# MOSFET_Board.net
KiCad netlist of a schematic drawn in EAGLE
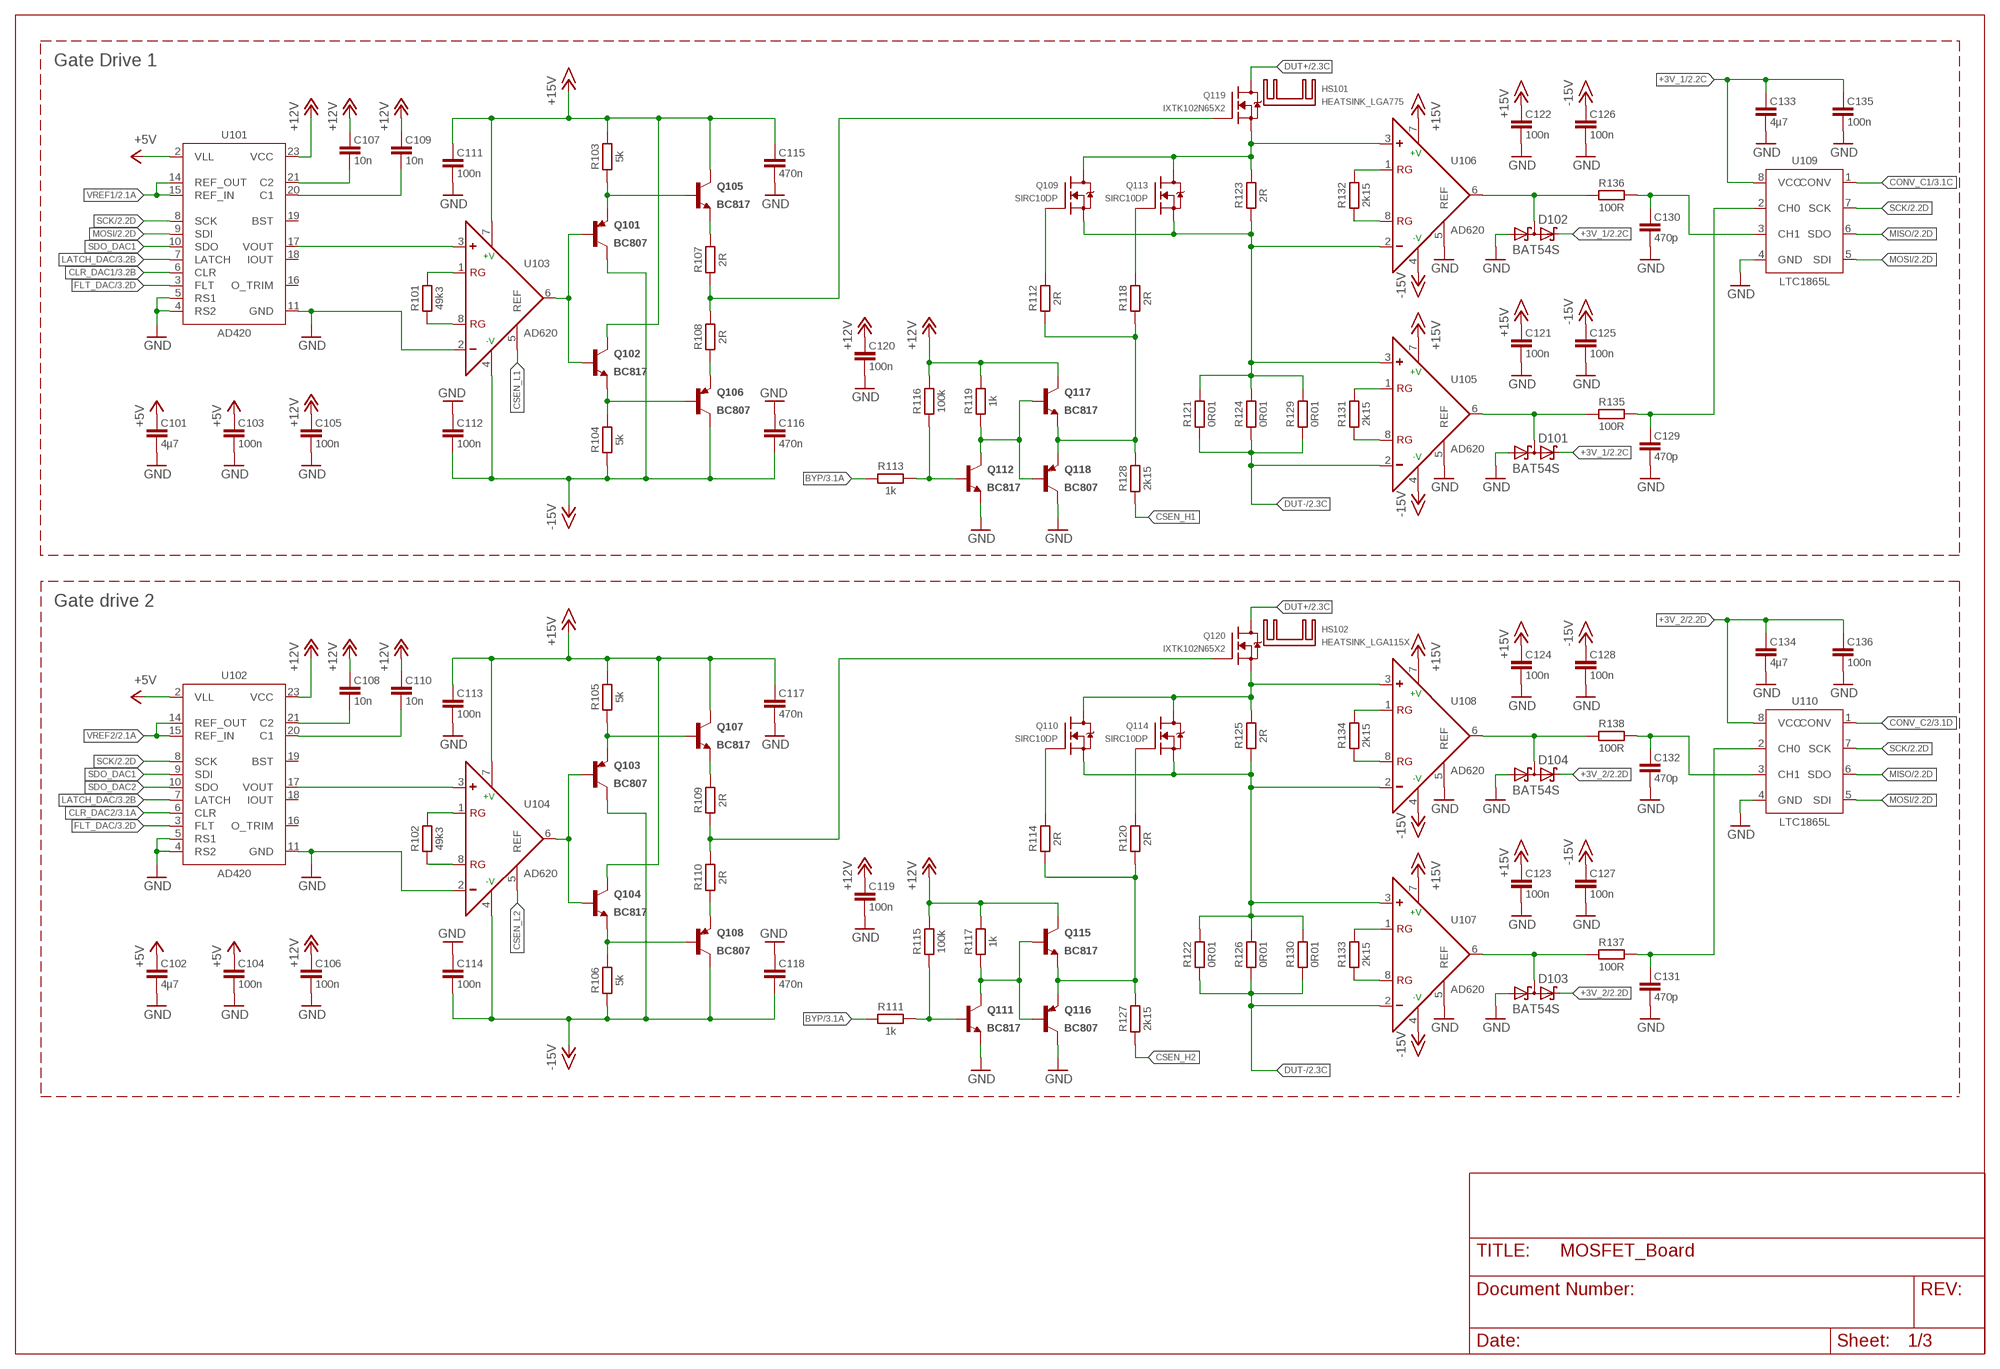
[diagram p0: schematic, sheet 1]
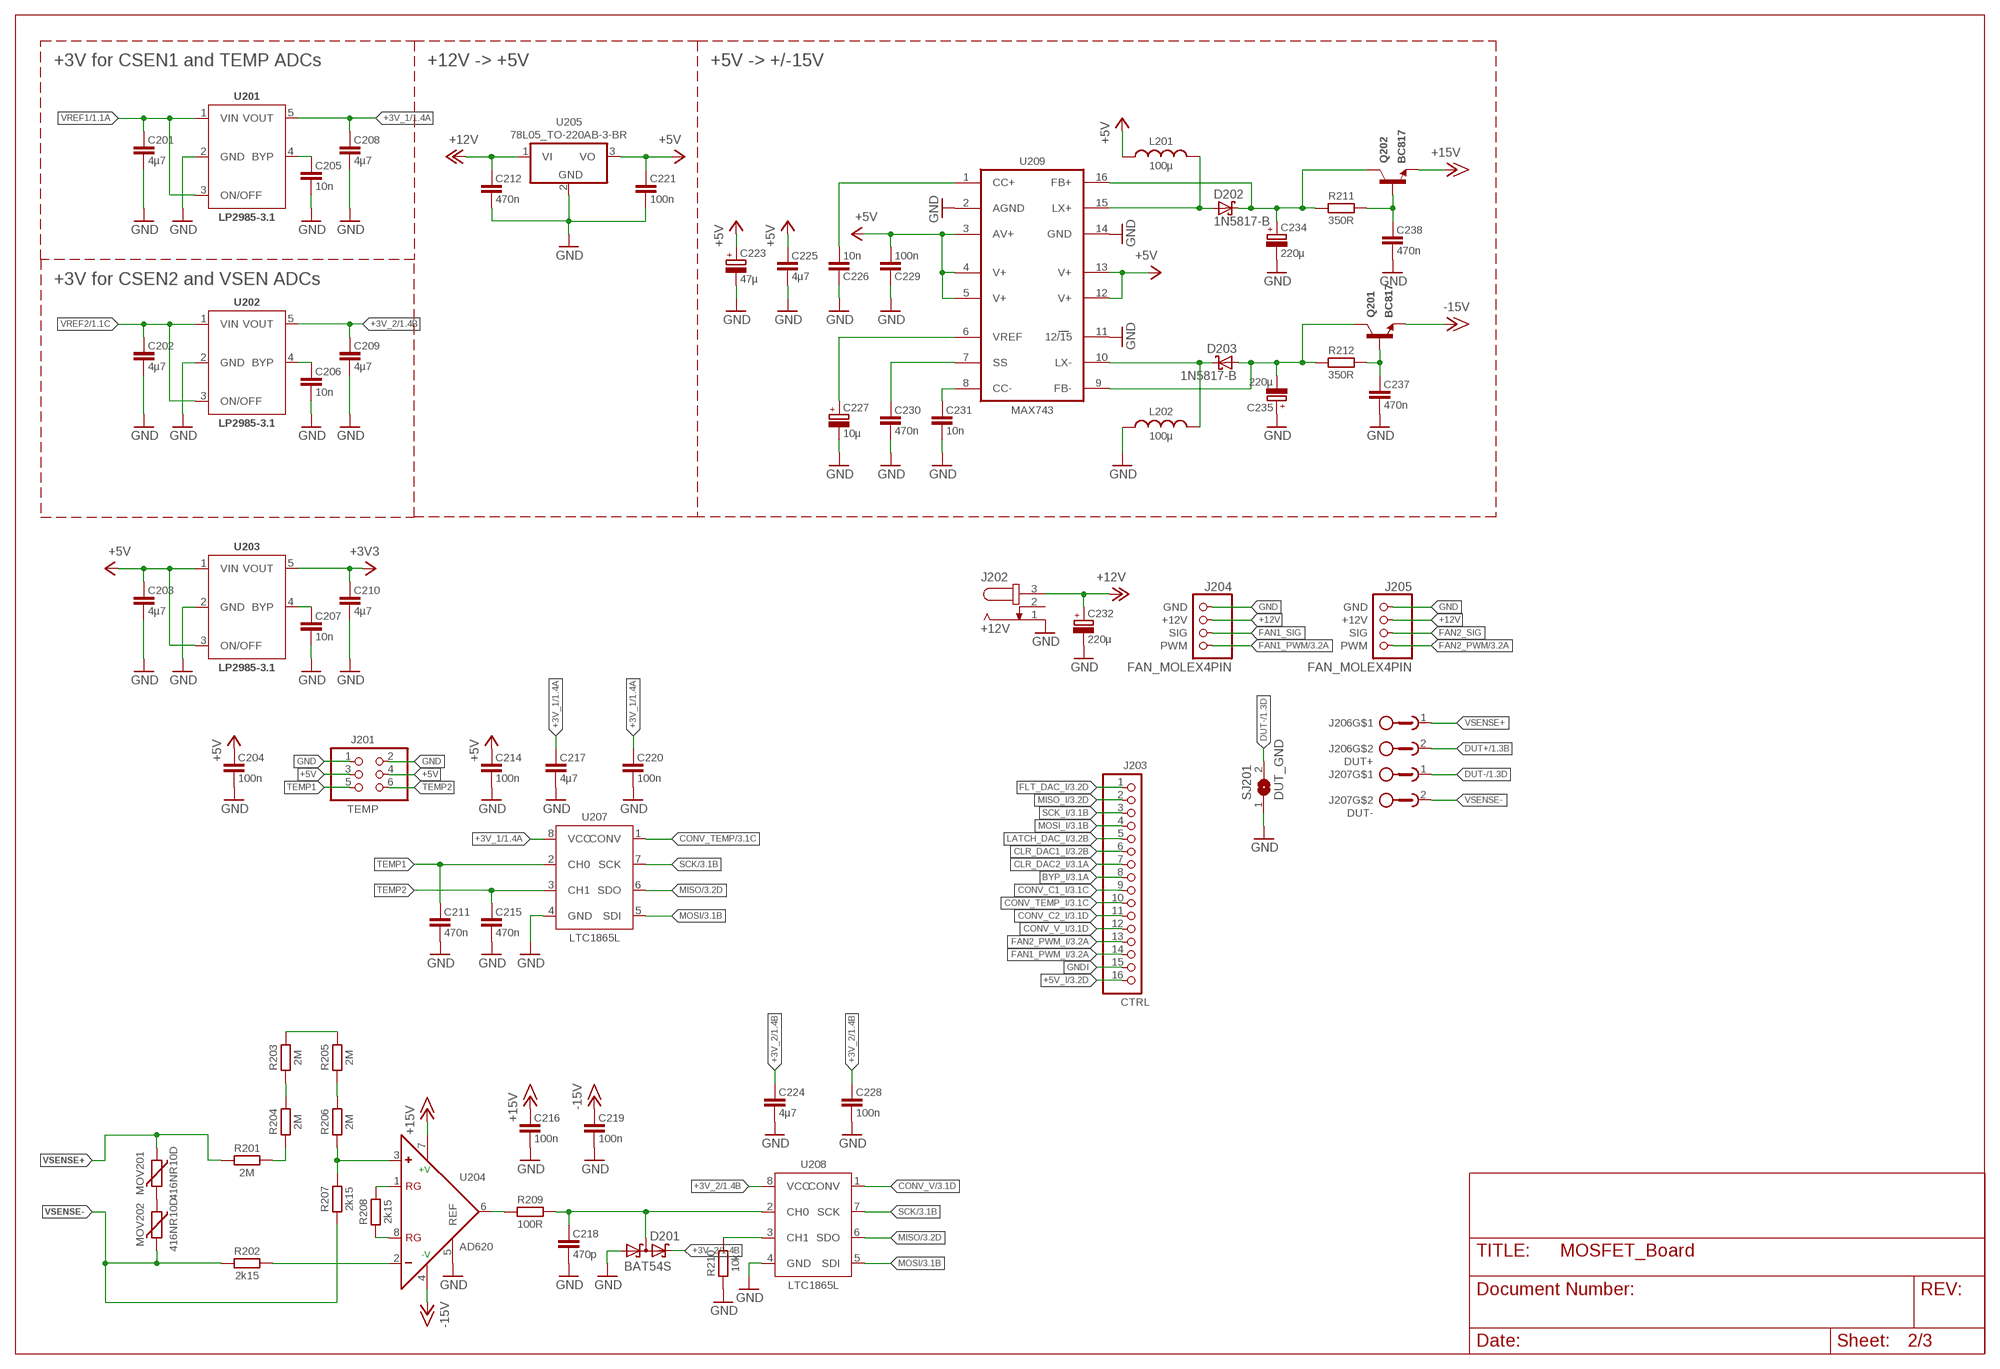
[diagram p1: schematic, sheet 2]
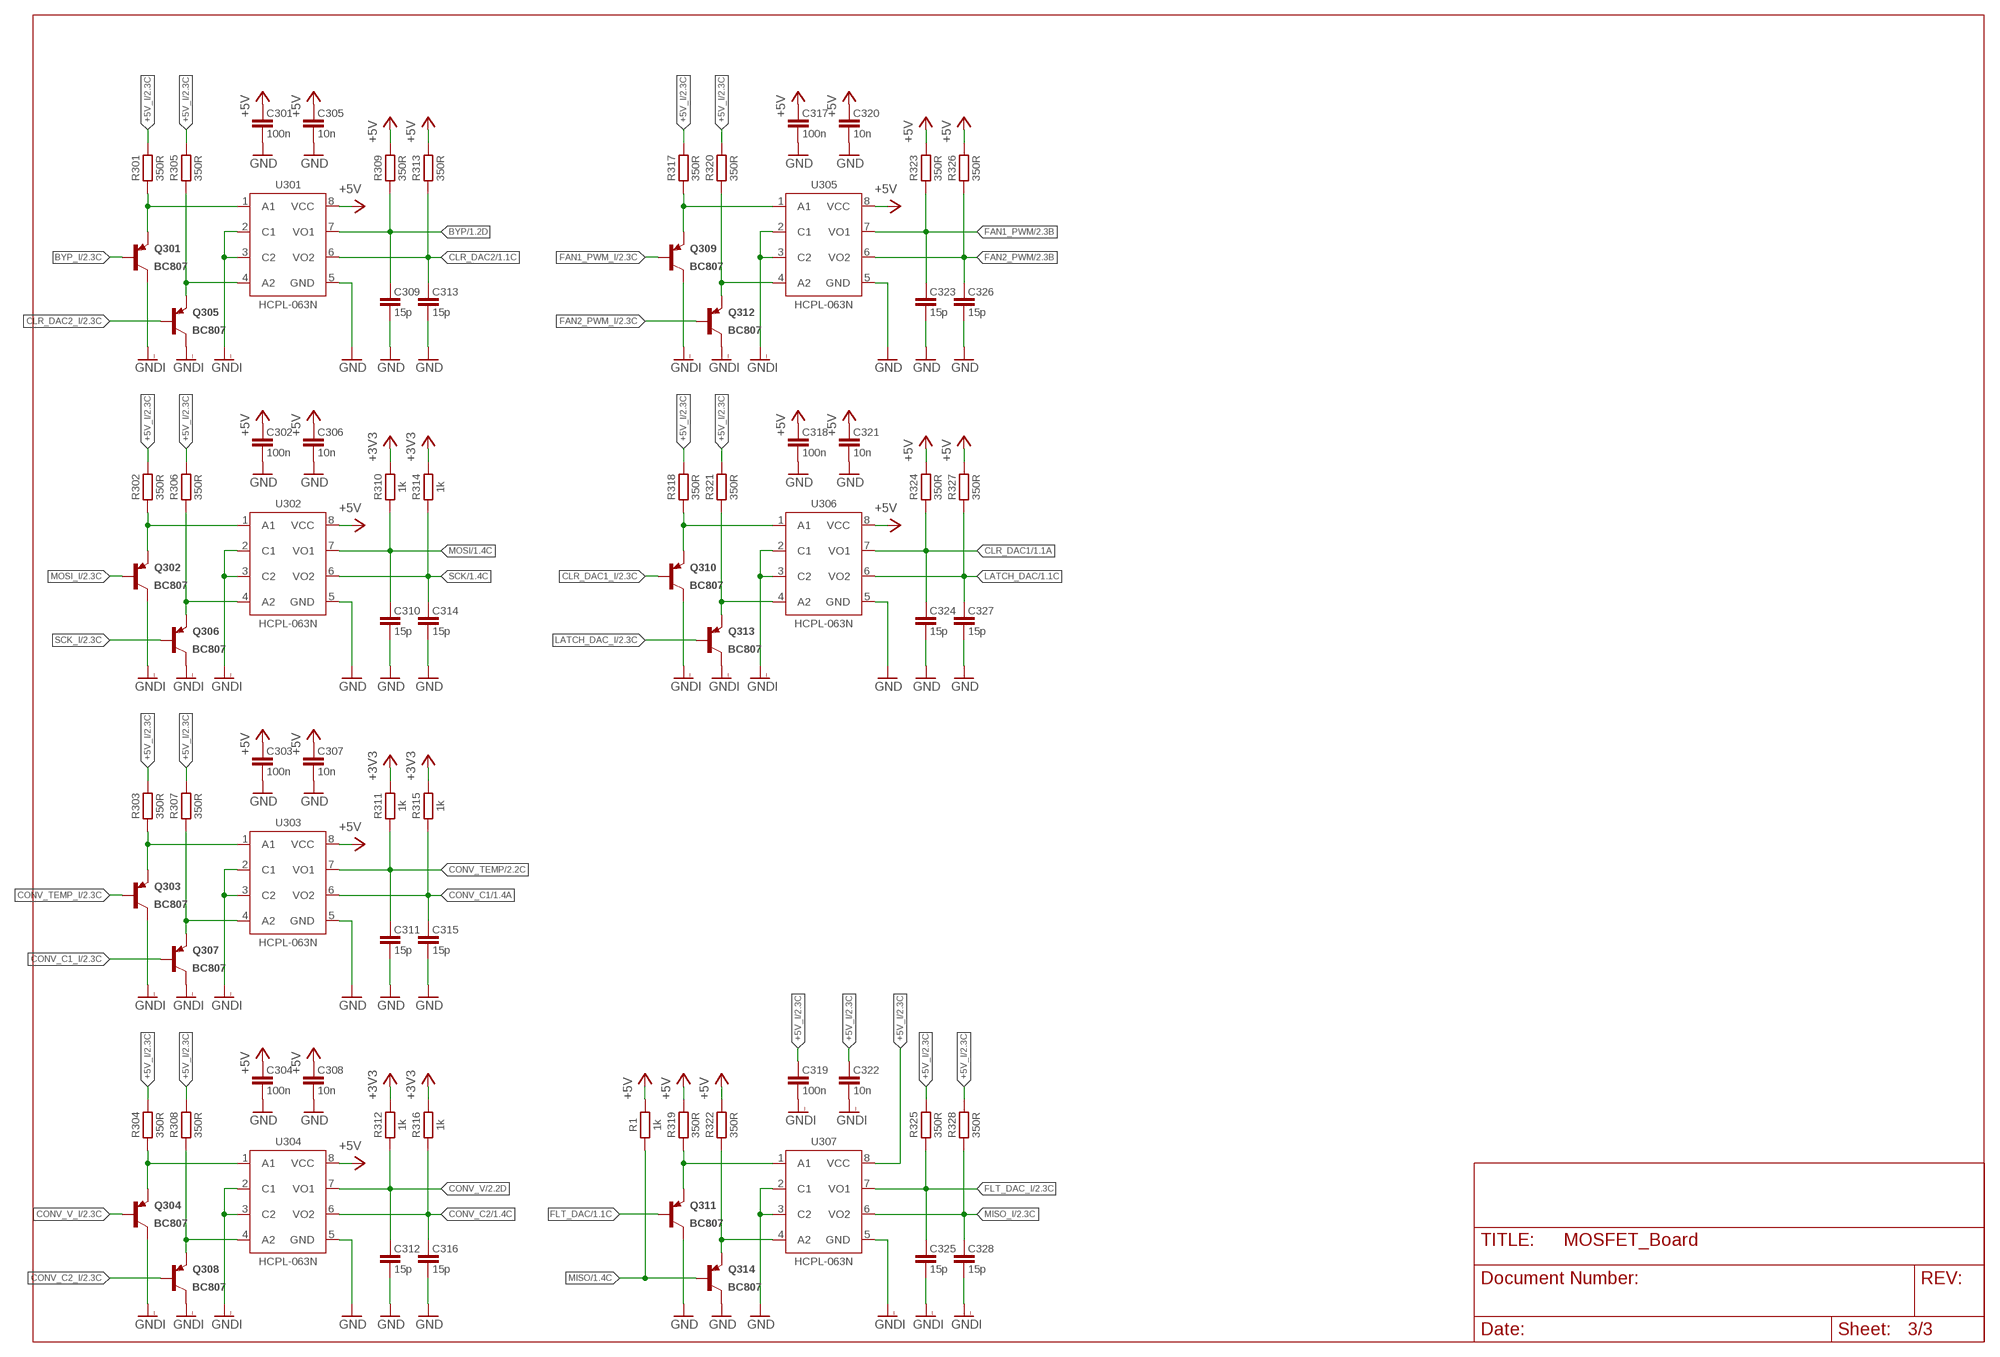
[diagram p2: schematic, sheet 3]

(export (version "E")
  (design (tool "Eeschema 10.0.6"))
  (components
    (comp (ref "C101")
      (value "4µ7")
      (footprint "eagle-import:CAPC3216")
      (libsource (lib "eagle-import") (part "C-EU-3216"))
    )
    (comp (ref "C102")
      (value "4µ7")
      (footprint "eagle-import:CAPC3216")
      (libsource (lib "eagle-import") (part "C-EU-3216"))
    )
    (comp (ref "C103")
      (value "100n")
      (footprint "eagle-import:CAPC1608")
      (libsource (lib "eagle-import") (part "C-EU-1608"))
    )
    (comp (ref "C104")
      (value "100n")
      (footprint "eagle-import:CAPC1608")
      (libsource (lib "eagle-import") (part "C-EU-1608"))
    )
    (comp (ref "C105")
      (value "100n")
      (footprint "eagle-import:CAPC1608")
      (libsource (lib "eagle-import") (part "C-EU-1608"))
    )
    (comp (ref "C106")
      (value "100n")
      (footprint "eagle-import:CAPC1608")
      (libsource (lib "eagle-import") (part "C-EU-1608"))
    )
    (comp (ref "C107")
      (value "10n")
      (footprint "eagle-import:CAPC2012")
      (libsource (lib "eagle-import") (part "C-EU-2012"))
    )
    (comp (ref "C108")
      (value "10n")
      (footprint "eagle-import:CAPC2012")
      (libsource (lib "eagle-import") (part "C-EU-2012"))
    )
    (comp (ref "C109")
      (value "10n")
      (footprint "eagle-import:CAPC2012")
      (libsource (lib "eagle-import") (part "C-EU-2012"))
    )
    (comp (ref "C110")
      (value "10n")
      (footprint "eagle-import:CAPC2012")
      (libsource (lib "eagle-import") (part "C-EU-2012"))
    )
    (comp (ref "C111")
      (value "100n")
      (footprint "eagle-import:CAPC1608")
      (libsource (lib "eagle-import") (part "C-EU-1608"))
    )
    (comp (ref "C112")
      (value "100n")
      (footprint "eagle-import:CAPC1608")
      (libsource (lib "eagle-import") (part "C-EU-1608"))
    )
    (comp (ref "C113")
      (value "100n")
      (footprint "eagle-import:CAPC1608")
      (libsource (lib "eagle-import") (part "C-EU-1608"))
    )
    (comp (ref "C114")
      (value "100n")
      (footprint "eagle-import:CAPC1608")
      (libsource (lib "eagle-import") (part "C-EU-1608"))
    )
    (comp (ref "C115")
      (value "470n")
      (footprint "eagle-import:CAPC1608")
      (libsource (lib "eagle-import") (part "C-EU-1608"))
    )
    (comp (ref "C116")
      (value "470n")
      (footprint "eagle-import:CAPC1608")
      (libsource (lib "eagle-import") (part "C-EU-1608"))
    )
    (comp (ref "C117")
      (value "470n")
      (footprint "eagle-import:CAPC1608")
      (libsource (lib "eagle-import") (part "C-EU-1608"))
    )
    (comp (ref "C118")
      (value "470n")
      (footprint "eagle-import:CAPC1608")
      (libsource (lib "eagle-import") (part "C-EU-1608"))
    )
    (comp (ref "C119")
      (value "100n")
      (footprint "eagle-import:CAPC1608")
      (libsource (lib "eagle-import") (part "C-EU-1608"))
    )
    (comp (ref "C120")
      (value "100n")
      (footprint "eagle-import:CAPC1608")
      (libsource (lib "eagle-import") (part "C-EU-1608"))
    )
    (comp (ref "C121")
      (value "100n")
      (footprint "eagle-import:CAPC1608")
      (libsource (lib "eagle-import") (part "C-EU-1608"))
    )
    (comp (ref "C122")
      (value "100n")
      (footprint "eagle-import:CAPC1608")
      (libsource (lib "eagle-import") (part "C-EU-1608"))
    )
    (comp (ref "C123")
      (value "100n")
      (footprint "eagle-import:CAPC1608")
      (libsource (lib "eagle-import") (part "C-EU-1608"))
    )
    (comp (ref "C124")
      (value "100n")
      (footprint "eagle-import:CAPC1608")
      (libsource (lib "eagle-import") (part "C-EU-1608"))
    )
    (comp (ref "C125")
      (value "100n")
      (footprint "eagle-import:CAPC1608")
      (libsource (lib "eagle-import") (part "C-EU-1608"))
    )
    (comp (ref "C126")
      (value "100n")
      (footprint "eagle-import:CAPC1608")
      (libsource (lib "eagle-import") (part "C-EU-1608"))
    )
    (comp (ref "C127")
      (value "100n")
      (footprint "eagle-import:CAPC1608")
      (libsource (lib "eagle-import") (part "C-EU-1608"))
    )
    (comp (ref "C128")
      (value "100n")
      (footprint "eagle-import:CAPC1608")
      (libsource (lib "eagle-import") (part "C-EU-1608"))
    )
    (comp (ref "C129")
      (value "470p")
      (footprint "eagle-import:CAPC1608")
      (libsource (lib "eagle-import") (part "C-EU-1608"))
    )
    (comp (ref "C130")
      (value "470p")
      (footprint "eagle-import:CAPC1608")
      (libsource (lib "eagle-import") (part "C-EU-1608"))
    )
    (comp (ref "C131")
      (value "470p")
      (footprint "eagle-import:CAPC1608")
      (libsource (lib "eagle-import") (part "C-EU-1608"))
    )
    (comp (ref "C132")
      (value "470p")
      (footprint "eagle-import:CAPC1608")
      (libsource (lib "eagle-import") (part "C-EU-1608"))
    )
    (comp (ref "C133")
      (value "4µ7")
      (footprint "eagle-import:CAPC3216")
      (libsource (lib "eagle-import") (part "C-EU-3216"))
    )
    (comp (ref "C134")
      (value "4µ7")
      (footprint "eagle-import:CAPC3216")
      (libsource (lib "eagle-import") (part "C-EU-3216"))
    )
    (comp (ref "C135")
      (value "100n")
      (footprint "eagle-import:CAPC1608")
      (libsource (lib "eagle-import") (part "C-EU-1608"))
    )
    (comp (ref "C136")
      (value "100n")
      (footprint "eagle-import:CAPC1608")
      (libsource (lib "eagle-import") (part "C-EU-1608"))
    )
    (comp (ref "D101")
      (value "BAT54S")
      (footprint "eagle-import:SOT23")
      (libsource (lib "eagle-import") (part "BAT54S"))
    )
    (comp (ref "D102")
      (value "BAT54S")
      (footprint "eagle-import:SOT23")
      (libsource (lib "eagle-import") (part "BAT54S"))
    )
    (comp (ref "D103")
      (value "BAT54S")
      (footprint "eagle-import:SOT23")
      (libsource (lib "eagle-import") (part "BAT54S"))
    )
    (comp (ref "D104")
      (value "BAT54S")
      (footprint "eagle-import:SOT23")
      (libsource (lib "eagle-import") (part "BAT54S"))
    )
    (comp (ref "HS101")
      (value "HEATSINK_LGA775")
      (footprint "eagle-import:D95263-001")
      (libsource (lib "eagle-import") (part "HEATSINK_LGA775"))
    )
    (comp (ref "HS102")
      (value "HEATSINK_LGA115X")
      (footprint "eagle-import:E97378-001")
      (libsource (lib "eagle-import") (part "HEATSINK_LGA115X"))
    )
    (comp (ref "Q101")
      (value "BC807")
      (footprint "eagle-import:SOT23")
      (libsource (lib "eagle-import") (part "BC807"))
    )
    (comp (ref "Q102")
      (value "BC817")
      (footprint "eagle-import:SOT23")
      (libsource (lib "eagle-import") (part "BC817"))
    )
    (comp (ref "Q103")
      (value "BC807")
      (footprint "eagle-import:SOT23")
      (libsource (lib "eagle-import") (part "BC807"))
    )
    (comp (ref "Q104")
      (value "BC817")
      (footprint "eagle-import:SOT23")
      (libsource (lib "eagle-import") (part "BC817"))
    )
    (comp (ref "Q105")
      (value "BC817")
      (footprint "eagle-import:SOT23")
      (libsource (lib "eagle-import") (part "BC817"))
    )
    (comp (ref "Q106")
      (value "BC807")
      (footprint "eagle-import:SOT23")
      (libsource (lib "eagle-import") (part "BC807"))
    )
    (comp (ref "Q107")
      (value "BC817")
      (footprint "eagle-import:SOT23")
      (libsource (lib "eagle-import") (part "BC817"))
    )
    (comp (ref "Q108")
      (value "BC807")
      (footprint "eagle-import:SOT23")
      (libsource (lib "eagle-import") (part "BC807"))
    )
    (comp (ref "Q109")
      (value "SIRC10DP")
      (footprint "eagle-import:POWERPAK-SO-8")
      (libsource (lib "eagle-import") (part "SIRC10DP"))
    )
    (comp (ref "Q110")
      (value "SIRC10DP")
      (footprint "eagle-import:POWERPAK-SO-8")
      (libsource (lib "eagle-import") (part "SIRC10DP"))
    )
    (comp (ref "Q111")
      (value "BC817")
      (footprint "eagle-import:SOT23")
      (libsource (lib "eagle-import") (part "BC817"))
    )
    (comp (ref "Q112")
      (value "BC817")
      (footprint "eagle-import:SOT23")
      (libsource (lib "eagle-import") (part "BC817"))
    )
    (comp (ref "Q113")
      (value "SIRC10DP")
      (footprint "eagle-import:POWERPAK-SO-8")
      (libsource (lib "eagle-import") (part "SIRC10DP"))
    )
    (comp (ref "Q114")
      (value "SIRC10DP")
      (footprint "eagle-import:POWERPAK-SO-8")
      (libsource (lib "eagle-import") (part "SIRC10DP"))
    )
    (comp (ref "Q115")
      (value "BC817")
      (footprint "eagle-import:SOT23")
      (libsource (lib "eagle-import") (part "BC817"))
    )
    (comp (ref "Q116")
      (value "BC807")
      (footprint "eagle-import:SOT23")
      (libsource (lib "eagle-import") (part "BC807"))
    )
    (comp (ref "Q117")
      (value "BC817")
      (footprint "eagle-import:SOT23")
      (libsource (lib "eagle-import") (part "BC817"))
    )
    (comp (ref "Q118")
      (value "BC807")
      (footprint "eagle-import:SOT23")
      (libsource (lib "eagle-import") (part "BC807"))
    )
    (comp (ref "Q119")
      (value "IXTK102N65X2")
      (footprint "eagle-import:TO-264P-H-PADUP")
      (libsource (lib "eagle-import") (part "IXTK102N65X2R"))
    )
    (comp (ref "Q120")
      (value "IXTK102N65X2")
      (footprint "eagle-import:TO-264P-H-PADUP")
      (libsource (lib "eagle-import") (part "IXTK102N65X2R"))
    )
    (comp (ref "R101")
      (value "49k3")
      (footprint "eagle-import:RESC1608")
      (libsource (lib "eagle-import") (part "R-EU-1608"))
    )
    (comp (ref "R102")
      (value "49k3")
      (footprint "eagle-import:RESC1608")
      (libsource (lib "eagle-import") (part "R-EU-1608"))
    )
    (comp (ref "R103")
      (value "5k")
      (footprint "eagle-import:RESC1608")
      (libsource (lib "eagle-import") (part "R-EU-1608"))
    )
    (comp (ref "R104")
      (value "5k")
      (footprint "eagle-import:RESC1608")
      (libsource (lib "eagle-import") (part "R-EU-1608"))
    )
    (comp (ref "R105")
      (value "5k")
      (footprint "eagle-import:RESC1608")
      (libsource (lib "eagle-import") (part "R-EU-1608"))
    )
    (comp (ref "R106")
      (value "5k")
      (footprint "eagle-import:RESC1608")
      (libsource (lib "eagle-import") (part "R-EU-1608"))
    )
    (comp (ref "R107")
      (value "2R")
      (footprint "eagle-import:RESC3216")
      (libsource (lib "eagle-import") (part "R-EU-3216"))
    )
    (comp (ref "R108")
      (value "2R")
      (footprint "eagle-import:RESC3216")
      (libsource (lib "eagle-import") (part "R-EU-3216"))
    )
    (comp (ref "R109")
      (value "2R")
      (footprint "eagle-import:RESC3216")
      (libsource (lib "eagle-import") (part "R-EU-3216"))
    )
    (comp (ref "R110")
      (value "2R")
      (footprint "eagle-import:RESC3216")
      (libsource (lib "eagle-import") (part "R-EU-3216"))
    )
    (comp (ref "R111")
      (value "1k")
      (footprint "eagle-import:RESC1608")
      (libsource (lib "eagle-import") (part "R-EU-1608"))
    )
    (comp (ref "R112")
      (value "2R")
      (footprint "eagle-import:RESC3216")
      (libsource (lib "eagle-import") (part "R-EU-3216"))
    )
    (comp (ref "R113")
      (value "1k")
      (footprint "eagle-import:RESC1608")
      (libsource (lib "eagle-import") (part "R-EU-1608"))
    )
    (comp (ref "R114")
      (value "2R")
      (footprint "eagle-import:RESC3216")
      (libsource (lib "eagle-import") (part "R-EU-3216"))
    )
    (comp (ref "R115")
      (value "100k")
      (footprint "eagle-import:RESC1608")
      (libsource (lib "eagle-import") (part "R-EU-1608"))
    )
    (comp (ref "R116")
      (value "100k")
      (footprint "eagle-import:RESC1608")
      (libsource (lib "eagle-import") (part "R-EU-1608"))
    )
    (comp (ref "R117")
      (value "1k")
      (footprint "eagle-import:RESC1608")
      (libsource (lib "eagle-import") (part "R-EU-1608"))
    )
    (comp (ref "R118")
      (value "2R")
      (footprint "eagle-import:RESC3216")
      (libsource (lib "eagle-import") (part "R-EU-3216"))
    )
    (comp (ref "R119")
      (value "1k")
      (footprint "eagle-import:RESC1608")
      (libsource (lib "eagle-import") (part "R-EU-1608"))
    )
    (comp (ref "R120")
      (value "2R")
      (footprint "eagle-import:RESC3216")
      (libsource (lib "eagle-import") (part "R-EU-3216"))
    )
    (comp (ref "R121")
      (value "0R01")
      (footprint "eagle-import:RESC6332")
      (libsource (lib "eagle-import") (part "R-EU-6332"))
    )
    (comp (ref "R122")
      (value "0R01")
      (footprint "eagle-import:RESC6332")
      (libsource (lib "eagle-import") (part "R-EU-6332"))
    )
    (comp (ref "R123")
      (value "2R")
      (footprint "eagle-import:RESC3216")
      (libsource (lib "eagle-import") (part "R-EU-3216"))
    )
    (comp (ref "R124")
      (value "0R01")
      (footprint "eagle-import:RESC6332")
      (libsource (lib "eagle-import") (part "R-EU-6332"))
    )
    (comp (ref "R125")
      (value "2R")
      (footprint "eagle-import:RESC3216")
      (libsource (lib "eagle-import") (part "R-EU-3216"))
    )
    (comp (ref "R126")
      (value "0R01")
      (footprint "eagle-import:RESC6332")
      (libsource (lib "eagle-import") (part "R-EU-6332"))
    )
    (comp (ref "R127")
      (value "2k15")
      (footprint "eagle-import:RESC2012")
      (libsource (lib "eagle-import") (part "R-EU-2012"))
    )
    (comp (ref "R128")
      (value "2k15")
      (footprint "eagle-import:RESC2012")
      (libsource (lib "eagle-import") (part "R-EU-2012"))
    )
    (comp (ref "R129")
      (value "0R01")
      (footprint "eagle-import:RESC6332")
      (libsource (lib "eagle-import") (part "R-EU-6332"))
    )
    (comp (ref "R130")
      (value "0R01")
      (footprint "eagle-import:RESC6332")
      (libsource (lib "eagle-import") (part "R-EU-6332"))
    )
    (comp (ref "R131")
      (value "2k15")
      (footprint "eagle-import:RESC2012")
      (libsource (lib "eagle-import") (part "R-EU-2012"))
    )
    (comp (ref "R132")
      (value "2k15")
      (footprint "eagle-import:RESC2012")
      (libsource (lib "eagle-import") (part "R-EU-2012"))
    )
    (comp (ref "R133")
      (value "2k15")
      (footprint "eagle-import:RESC2012")
      (libsource (lib "eagle-import") (part "R-EU-2012"))
    )
    (comp (ref "R134")
      (value "2k15")
      (footprint "eagle-import:RESC2012")
      (libsource (lib "eagle-import") (part "R-EU-2012"))
    )
    (comp (ref "R135")
      (value "100R")
      (footprint "eagle-import:RESC1608")
      (libsource (lib "eagle-import") (part "R-EU-1608"))
    )
    (comp (ref "R136")
      (value "100R")
      (footprint "eagle-import:RESC1608")
      (libsource (lib "eagle-import") (part "R-EU-1608"))
    )
    (comp (ref "R137")
      (value "100R")
      (footprint "eagle-import:RESC1608")
      (libsource (lib "eagle-import") (part "R-EU-1608"))
    )
    (comp (ref "R138")
      (value "100R")
      (footprint "eagle-import:RESC1608")
      (libsource (lib "eagle-import") (part "R-EU-1608"))
    )
    (comp (ref "U101")
      (value "AD420")
      (footprint "eagle-import:SO24W")
      (libsource (lib "eagle-import") (part "AD420RW-24"))
    )
    (comp (ref "U102")
      (value "AD420")
      (footprint "eagle-import:SO24W")
      (libsource (lib "eagle-import") (part "AD420RW-24"))
    )
    (comp (ref "U103")
      (value "AD620")
      (footprint "eagle-import:SO8")
      (libsource (lib "eagle-import") (part "AD620R-8"))
    )
    (comp (ref "U104")
      (value "AD620")
      (footprint "eagle-import:SO8")
      (libsource (lib "eagle-import") (part "AD620R-8"))
    )
    (comp (ref "U105")
      (value "AD620")
      (footprint "eagle-import:SO8")
      (libsource (lib "eagle-import") (part "AD620R-8"))
    )
    (comp (ref "U106")
      (value "AD620")
      (footprint "eagle-import:SO8")
      (libsource (lib "eagle-import") (part "AD620R-8"))
    )
    (comp (ref "U107")
      (value "AD620")
      (footprint "eagle-import:SO8")
      (libsource (lib "eagle-import") (part "AD620R-8"))
    )
    (comp (ref "U108")
      (value "AD620")
      (footprint "eagle-import:SO8")
      (libsource (lib "eagle-import") (part "AD620R-8"))
    )
    (comp (ref "U109")
      (value "LTC1865L")
      (footprint "eagle-import:SO8")
      (libsource (lib "eagle-import") (part "LTC1865L"))
    )
    (comp (ref "U110")
      (value "LTC1865L")
      (footprint "eagle-import:SO8")
      (libsource (lib "eagle-import") (part "LTC1865L"))
    )
    (comp (ref "C301")
      (value "100n")
      (footprint "eagle-import:CAPC1608")
      (libsource (lib "eagle-import") (part "C-EU-1608"))
    )
    (comp (ref "C302")
      (value "100n")
      (footprint "eagle-import:CAPC1608")
      (libsource (lib "eagle-import") (part "C-EU-1608"))
    )
    (comp (ref "C303")
      (value "100n")
      (footprint "eagle-import:CAPC1608")
      (libsource (lib "eagle-import") (part "C-EU-1608"))
    )
    (comp (ref "C304")
      (value "100n")
      (footprint "eagle-import:CAPC1608")
      (libsource (lib "eagle-import") (part "C-EU-1608"))
    )
    (comp (ref "C305")
      (value "10n")
      (footprint "eagle-import:CAPC1608")
      (libsource (lib "eagle-import") (part "C-EU-1608"))
    )
    (comp (ref "C306")
      (value "10n")
      (footprint "eagle-import:CAPC1608")
      (libsource (lib "eagle-import") (part "C-EU-1608"))
    )
    (comp (ref "C307")
      (value "10n")
      (footprint "eagle-import:CAPC1608")
      (libsource (lib "eagle-import") (part "C-EU-1608"))
    )
    (comp (ref "C308")
      (value "10n")
      (footprint "eagle-import:CAPC1608")
      (libsource (lib "eagle-import") (part "C-EU-1608"))
    )
    (comp (ref "C309")
      (value "15p")
      (footprint "eagle-import:CAPC1608")
      (libsource (lib "eagle-import") (part "C-EU-1608"))
    )
    (comp (ref "C310")
      (value "15p")
      (footprint "eagle-import:CAPC1608")
      (libsource (lib "eagle-import") (part "C-EU-1608"))
    )
    (comp (ref "C311")
      (value "15p")
      (footprint "eagle-import:CAPC1608")
      (libsource (lib "eagle-import") (part "C-EU-1608"))
    )
    (comp (ref "C312")
      (value "15p")
      (footprint "eagle-import:CAPC1608")
      (libsource (lib "eagle-import") (part "C-EU-1608"))
    )
    (comp (ref "C313")
      (value "15p")
      (footprint "eagle-import:CAPC1608")
      (libsource (lib "eagle-import") (part "C-EU-1608"))
    )
    (comp (ref "C314")
      (value "15p")
      (footprint "eagle-import:CAPC1608")
      (libsource (lib "eagle-import") (part "C-EU-1608"))
    )
    (comp (ref "C315")
      (value "15p")
      (footprint "eagle-import:CAPC1608")
      (libsource (lib "eagle-import") (part "C-EU-1608"))
    )
    (comp (ref "C316")
      (value "15p")
      (footprint "eagle-import:CAPC1608")
      (libsource (lib "eagle-import") (part "C-EU-1608"))
    )
    (comp (ref "C317")
      (value "100n")
      (footprint "eagle-import:CAPC1608")
      (libsource (lib "eagle-import") (part "C-EU-1608"))
    )
    (comp (ref "C318")
      (value "100n")
      (footprint "eagle-import:CAPC1608")
      (libsource (lib "eagle-import") (part "C-EU-1608"))
    )
    (comp (ref "C319")
      (value "100n")
      (footprint "eagle-import:CAPC1608")
      (libsource (lib "eagle-import") (part "C-EU-1608"))
    )
    (comp (ref "C320")
      (value "10n")
      (footprint "eagle-import:CAPC1608")
      (libsource (lib "eagle-import") (part "C-EU-1608"))
    )
    (comp (ref "C321")
      (value "10n")
      (footprint "eagle-import:CAPC1608")
      (libsource (lib "eagle-import") (part "C-EU-1608"))
    )
    (comp (ref "C322")
      (value "10n")
      (footprint "eagle-import:CAPC1608")
      (libsource (lib "eagle-import") (part "C-EU-1608"))
    )
    (comp (ref "C323")
      (value "15p")
      (footprint "eagle-import:CAPC1608")
      (libsource (lib "eagle-import") (part "C-EU-1608"))
    )
    (comp (ref "C324")
      (value "15p")
      (footprint "eagle-import:CAPC1608")
      (libsource (lib "eagle-import") (part "C-EU-1608"))
    )
    (comp (ref "C325")
      (value "15p")
      (footprint "eagle-import:CAPC1608")
      (libsource (lib "eagle-import") (part "C-EU-1608"))
    )
    (comp (ref "C326")
      (value "15p")
      (footprint "eagle-import:CAPC1608")
      (libsource (lib "eagle-import") (part "C-EU-1608"))
    )
    (comp (ref "C327")
      (value "15p")
      (footprint "eagle-import:CAPC1608")
      (libsource (lib "eagle-import") (part "C-EU-1608"))
    )
    (comp (ref "C328")
      (value "15p")
      (footprint "eagle-import:CAPC1608")
      (libsource (lib "eagle-import") (part "C-EU-1608"))
    )
    (comp (ref "Q301")
      (value "BC807")
      (footprint "eagle-import:SOT23")
      (libsource (lib "eagle-import") (part "BC807"))
    )
    (comp (ref "Q302")
      (value "BC807")
      (footprint "eagle-import:SOT23")
      (libsource (lib "eagle-import") (part "BC807"))
    )
    (comp (ref "Q303")
      (value "BC807")
      (footprint "eagle-import:SOT23")
      (libsource (lib "eagle-import") (part "BC807"))
    )
    (comp (ref "Q304")
      (value "BC807")
      (footprint "eagle-import:SOT23")
      (libsource (lib "eagle-import") (part "BC807"))
    )
    (comp (ref "Q305")
      (value "BC807")
      (footprint "eagle-import:SOT23")
      (libsource (lib "eagle-import") (part "BC807"))
    )
    (comp (ref "Q306")
      (value "BC807")
      (footprint "eagle-import:SOT23")
      (libsource (lib "eagle-import") (part "BC807"))
    )
    (comp (ref "Q307")
      (value "BC807")
      (footprint "eagle-import:SOT23")
      (libsource (lib "eagle-import") (part "BC807"))
    )
    (comp (ref "Q308")
      (value "BC807")
      (footprint "eagle-import:SOT23")
      (libsource (lib "eagle-import") (part "BC807"))
    )
    (comp (ref "Q309")
      (value "BC807")
      (footprint "eagle-import:SOT23")
      (libsource (lib "eagle-import") (part "BC807"))
    )
    (comp (ref "Q310")
      (value "BC807")
      (footprint "eagle-import:SOT23")
      (libsource (lib "eagle-import") (part "BC807"))
    )
    (comp (ref "Q311")
      (value "BC807")
      (footprint "eagle-import:SOT23")
      (libsource (lib "eagle-import") (part "BC807"))
    )
    (comp (ref "Q312")
      (value "BC807")
      (footprint "eagle-import:SOT23")
      (libsource (lib "eagle-import") (part "BC807"))
    )
    (comp (ref "Q313")
      (value "BC807")
      (footprint "eagle-import:SOT23")
      (libsource (lib "eagle-import") (part "BC807"))
    )
    (comp (ref "Q314")
      (value "BC807")
      (footprint "eagle-import:SOT23")
      (libsource (lib "eagle-import") (part "BC807"))
    )
    (comp (ref "R1")
      (value "1k")
      (footprint "eagle-import:RESC1608")
      (libsource (lib "eagle-import") (part "R-EU-1608"))
    )
    (comp (ref "R301")
      (value "350R")
      (footprint "eagle-import:RESC1608")
      (libsource (lib "eagle-import") (part "R-EU-1608"))
    )
    (comp (ref "R302")
      (value "350R")
      (footprint "eagle-import:RESC1608")
      (libsource (lib "eagle-import") (part "R-EU-1608"))
    )
    (comp (ref "R303")
      (value "350R")
      (footprint "eagle-import:RESC1608")
      (libsource (lib "eagle-import") (part "R-EU-1608"))
    )
    (comp (ref "R304")
      (value "350R")
      (footprint "eagle-import:RESC1608")
      (libsource (lib "eagle-import") (part "R-EU-1608"))
    )
    (comp (ref "R305")
      (value "350R")
      (footprint "eagle-import:RESC1608")
      (libsource (lib "eagle-import") (part "R-EU-1608"))
    )
    (comp (ref "R306")
      (value "350R")
      (footprint "eagle-import:RESC1608")
      (libsource (lib "eagle-import") (part "R-EU-1608"))
    )
    (comp (ref "R307")
      (value "350R")
      (footprint "eagle-import:RESC1608")
      (libsource (lib "eagle-import") (part "R-EU-1608"))
    )
    (comp (ref "R308")
      (value "350R")
      (footprint "eagle-import:RESC1608")
      (libsource (lib "eagle-import") (part "R-EU-1608"))
    )
    (comp (ref "R309")
      (value "350R")
      (footprint "eagle-import:RESC1608")
      (libsource (lib "eagle-import") (part "R-EU-1608"))
    )
    (comp (ref "R310")
      (value "1k")
      (footprint "eagle-import:RESC1608")
      (libsource (lib "eagle-import") (part "R-EU-1608"))
    )
    (comp (ref "R311")
      (value "1k")
      (footprint "eagle-import:RESC1608")
      (libsource (lib "eagle-import") (part "R-EU-1608"))
    )
    (comp (ref "R312")
      (value "1k")
      (footprint "eagle-import:RESC1608")
      (libsource (lib "eagle-import") (part "R-EU-1608"))
    )
    (comp (ref "R313")
      (value "350R")
      (footprint "eagle-import:RESC1608")
      (libsource (lib "eagle-import") (part "R-EU-1608"))
    )
    (comp (ref "R314")
      (value "1k")
      (footprint "eagle-import:RESC1608")
      (libsource (lib "eagle-import") (part "R-EU-1608"))
    )
    (comp (ref "R315")
      (value "1k")
      (footprint "eagle-import:RESC1608")
      (libsource (lib "eagle-import") (part "R-EU-1608"))
    )
    (comp (ref "R316")
      (value "1k")
      (footprint "eagle-import:RESC1608")
      (libsource (lib "eagle-import") (part "R-EU-1608"))
    )
    (comp (ref "R317")
      (value "350R")
      (footprint "eagle-import:RESC1608")
      (libsource (lib "eagle-import") (part "R-EU-1608"))
    )
    (comp (ref "R318")
      (value "350R")
      (footprint "eagle-import:RESC1608")
      (libsource (lib "eagle-import") (part "R-EU-1608"))
    )
    (comp (ref "R319")
      (value "350R")
      (footprint "eagle-import:RESC1608")
      (libsource (lib "eagle-import") (part "R-EU-1608"))
    )
    (comp (ref "R320")
      (value "350R")
      (footprint "eagle-import:RESC1608")
      (libsource (lib "eagle-import") (part "R-EU-1608"))
    )
    (comp (ref "R321")
      (value "350R")
      (footprint "eagle-import:RESC1608")
      (libsource (lib "eagle-import") (part "R-EU-1608"))
    )
    (comp (ref "R322")
      (value "350R")
      (footprint "eagle-import:RESC1608")
      (libsource (lib "eagle-import") (part "R-EU-1608"))
    )
    (comp (ref "R323")
      (value "350R")
      (footprint "eagle-import:RESC1608")
      (libsource (lib "eagle-import") (part "R-EU-1608"))
    )
    (comp (ref "R324")
      (value "350R")
      (footprint "eagle-import:RESC1608")
      (libsource (lib "eagle-import") (part "R-EU-1608"))
    )
    (comp (ref "R325")
      (value "350R")
      (footprint "eagle-import:RESC1608")
      (libsource (lib "eagle-import") (part "R-EU-1608"))
    )
    (comp (ref "R326")
      (value "350R")
      (footprint "eagle-import:RESC1608")
      (libsource (lib "eagle-import") (part "R-EU-1608"))
    )
    (comp (ref "R327")
      (value "350R")
      (footprint "eagle-import:RESC1608")
      (libsource (lib "eagle-import") (part "R-EU-1608"))
    )
    (comp (ref "R328")
      (value "350R")
      (footprint "eagle-import:RESC1608")
      (libsource (lib "eagle-import") (part "R-EU-1608"))
    )
    (comp (ref "U301")
      (value "HCPL-063N")
      (footprint "eagle-import:SO8")
      (libsource (lib "eagle-import") (part "HCPL-063N"))
    )
    (comp (ref "U302")
      (value "HCPL-063N")
      (footprint "eagle-import:SO8")
      (libsource (lib "eagle-import") (part "HCPL-063N"))
    )
    (comp (ref "U303")
      (value "HCPL-063N")
      (footprint "eagle-import:SO8")
      (libsource (lib "eagle-import") (part "HCPL-063N"))
    )
    (comp (ref "U304")
      (value "HCPL-063N")
      (footprint "eagle-import:SO8")
      (libsource (lib "eagle-import") (part "HCPL-063N"))
    )
    (comp (ref "U305")
      (value "HCPL-063N")
      (footprint "eagle-import:SO8")
      (libsource (lib "eagle-import") (part "HCPL-063N"))
    )
    (comp (ref "U306")
      (value "HCPL-063N")
      (footprint "eagle-import:SO8")
      (libsource (lib "eagle-import") (part "HCPL-063N"))
    )
    (comp (ref "U307")
      (value "HCPL-063N")
      (footprint "eagle-import:SO8")
      (libsource (lib "eagle-import") (part "HCPL-063N"))
    )
    (comp (ref "C201")
      (value "4µ7")
      (footprint "eagle-import:CAPC3216")
      (libsource (lib "eagle-import") (part "C-EU-3216"))
    )
    (comp (ref "C202")
      (value "4µ7")
      (footprint "eagle-import:CAPC3216")
      (libsource (lib "eagle-import") (part "C-EU-3216"))
    )
    (comp (ref "C203")
      (value "4µ7")
      (footprint "eagle-import:CAPC3216")
      (libsource (lib "eagle-import") (part "C-EU-3216"))
    )
    (comp (ref "C204")
      (value "100n")
      (footprint "eagle-import:CAPC1608")
      (libsource (lib "eagle-import") (part "C-EU-1608"))
    )
    (comp (ref "C205")
      (value "10n")
      (footprint "eagle-import:CAPC2012")
      (libsource (lib "eagle-import") (part "C-EU-2012"))
    )
    (comp (ref "C206")
      (value "10n")
      (footprint "eagle-import:CAPC2012")
      (libsource (lib "eagle-import") (part "C-EU-2012"))
    )
    (comp (ref "C207")
      (value "10n")
      (footprint "eagle-import:CAPC2012")
      (libsource (lib "eagle-import") (part "C-EU-2012"))
    )
    (comp (ref "C208")
      (value "4µ7")
      (footprint "eagle-import:CAPC3216")
      (libsource (lib "eagle-import") (part "C-EU-3216"))
    )
    (comp (ref "C209")
      (value "4µ7")
      (footprint "eagle-import:CAPC3216")
      (libsource (lib "eagle-import") (part "C-EU-3216"))
    )
    (comp (ref "C210")
      (value "4µ7")
      (footprint "eagle-import:CAPC3216")
      (libsource (lib "eagle-import") (part "C-EU-3216"))
    )
    (comp (ref "C211")
      (value "470n")
      (footprint "eagle-import:CAPC1608")
      (libsource (lib "eagle-import") (part "C-EU-1608"))
    )
    (comp (ref "C212")
      (value "470n")
      (footprint "eagle-import:CAPC1608")
      (libsource (lib "eagle-import") (part "C-EU-1608"))
    )
    (comp (ref "C214")
      (value "100n")
      (footprint "eagle-import:CAPC1608")
      (libsource (lib "eagle-import") (part "C-EU-1608"))
    )
    (comp (ref "C215")
      (value "470n")
      (footprint "eagle-import:CAPC1608")
      (libsource (lib "eagle-import") (part "C-EU-1608"))
    )
    (comp (ref "C216")
      (value "100n")
      (footprint "eagle-import:CAPC1608")
      (libsource (lib "eagle-import") (part "C-EU-1608"))
    )
    (comp (ref "C217")
      (value "4µ7")
      (footprint "eagle-import:CAPC3216")
      (libsource (lib "eagle-import") (part "C-EU-3216"))
    )
    (comp (ref "C218")
      (value "470p")
      (footprint "eagle-import:CAPC1608")
      (libsource (lib "eagle-import") (part "C-EU-1608"))
    )
    (comp (ref "C219")
      (value "100n")
      (footprint "eagle-import:CAPC1608")
      (libsource (lib "eagle-import") (part "C-EU-1608"))
    )
    (comp (ref "C220")
      (value "100n")
      (footprint "eagle-import:CAPC1608")
      (libsource (lib "eagle-import") (part "C-EU-1608"))
    )
    (comp (ref "C221")
      (value "100n")
      (footprint "eagle-import:CAPC1608")
      (libsource (lib "eagle-import") (part "C-EU-1608"))
    )
    (comp (ref "C223")
      (value "47µ")
      (footprint "eagle-import:CAPCP7343")
      (libsource (lib "eagle-import") (part "CPOL-7343-DE"))
    )
    (comp (ref "C224")
      (value "4µ7")
      (footprint "eagle-import:CAPC3216")
      (libsource (lib "eagle-import") (part "C-EU-3216"))
    )
    (comp (ref "C225")
      (value "4µ7")
      (footprint "eagle-import:CAPC3216")
      (libsource (lib "eagle-import") (part "C-EU-3216"))
    )
    (comp (ref "C226")
      (value "10n")
      (footprint "eagle-import:CAPC2012")
      (libsource (lib "eagle-import") (part "C-EU-2012"))
    )
    (comp (ref "C227")
      (value "10µ")
      (footprint "eagle-import:CAPCP6032")
      (libsource (lib "eagle-import") (part "CPOL-6032-C"))
    )
    (comp (ref "C228")
      (value "100n")
      (footprint "eagle-import:CAPC1608")
      (libsource (lib "eagle-import") (part "C-EU-1608"))
    )
    (comp (ref "C229")
      (value "100n")
      (footprint "eagle-import:CAPC1608")
      (libsource (lib "eagle-import") (part "C-EU-1608"))
    )
    (comp (ref "C230")
      (value "470n")
      (footprint "eagle-import:CAPC1608")
      (libsource (lib "eagle-import") (part "C-EU-1608"))
    )
    (comp (ref "C231")
      (value "10n")
      (footprint "eagle-import:CAPC2012")
      (libsource (lib "eagle-import") (part "C-EU-2012"))
    )
    (comp (ref "C232")
      (value "220µ")
      (footprint "eagle-import:CAPPRD500W60D1000H")
      (libsource (lib "eagle-import") (part "CPOL_CAPPRD500W60D1000"))
    )
    (comp (ref "C234")
      (value "220µ")
      (footprint "eagle-import:CAPPRD500W60D1000H")
      (libsource (lib "eagle-import") (part "CPOL_CAPPRD500W60D1000"))
    )
    (comp (ref "C235")
      (value "220µ")
      (footprint "eagle-import:CAPPRD500W60D1000H")
      (libsource (lib "eagle-import") (part "CPOL_CAPPRD500W60D1000"))
    )
    (comp (ref "C237")
      (value "470n")
      (footprint "eagle-import:CAPC1608")
      (libsource (lib "eagle-import") (part "C-EU-1608"))
    )
    (comp (ref "C238")
      (value "470n")
      (footprint "eagle-import:CAPC1608")
      (libsource (lib "eagle-import") (part "C-EU-1608"))
    )
    (comp (ref "D201")
      (value "BAT54S")
      (footprint "eagle-import:SOT23")
      (libsource (lib "eagle-import") (part "BAT54S"))
    )
    (comp (ref "D202")
      (value "1N5817-B")
      (footprint "eagle-import:DO41-7.6")
      (libsource (lib "eagle-import") (part "1N5817-B"))
    )
    (comp (ref "D203")
      (value "1N5817-B")
      (footprint "eagle-import:DO41-7.6")
      (libsource (lib "eagle-import") (part "1N5817-B"))
    )
    (comp (ref "J201")
      (value "TEMP")
      (footprint "eagle-import:HEAD_MALE_2X3")
      (libsource (lib "eagle-import") (part "HEAD_2X3_MALE"))
    )
    (comp (ref "J202")
      (value "+12V")
      (footprint "eagle-import:SPC4078")
      (libsource (lib "eagle-import") (part "JACK-PLUG1"))
    )
    (comp (ref "J203")
      (value "CTRL")
      (footprint "eagle-import:HEAD_MALE_1X16")
      (libsource (lib "eagle-import") (part "HEAD_1X16_MALE"))
    )
    (comp (ref "J204")
      (value "FAN_MOLEX4PIN")
      (footprint "eagle-import:MOLEX_47053-1000")
      (libsource (lib "eagle-import") (part "FAN_MOLEX4PIN"))
    )
    (comp (ref "J205")
      (value "FAN_MOLEX4PIN")
      (footprint "eagle-import:MOLEX_47053-1000")
      (libsource (lib "eagle-import") (part "FAN_MOLEX4PIN"))
    )
    (comp (ref "J206")
      (value "DUT+")
      (footprint "eagle-import:AMPHENOL-12-762_2")
      (libsource (lib "eagle-import") (part "AMPHENOL_TERM-BLOCK_2"))
    )
    (comp (ref "J207")
      (value "DUT-")
      (footprint "eagle-import:AMPHENOL-12-762_2")
      (libsource (lib "eagle-import") (part "AMPHENOL_TERM-BLOCK_2"))
    )
    (comp (ref "L201")
      (value "100µ")
      (footprint "eagle-import:MSS1260")
      (libsource (lib "eagle-import") (part "L-EU_MSS1260"))
    )
    (comp (ref "L202")
      (value "100µ")
      (footprint "eagle-import:MSS1260")
      (libsource (lib "eagle-import") (part "L-EU_MSS1260"))
    )
    (comp (ref "MOV201")
      (value "416NR10D")
      (footprint "eagle-import:DISK_9.5MM")
      (libsource (lib "eagle-import") (part "MOV_9.5-DISK"))
    )
    (comp (ref "MOV202")
      (value "416NR10D")
      (footprint "eagle-import:DISK_9.5MM")
      (libsource (lib "eagle-import") (part "MOV_9.5-DISK"))
    )
    (comp (ref "Q201")
      (value "BC817")
      (footprint "eagle-import:SOT23")
      (libsource (lib "eagle-import") (part "BC817"))
    )
    (comp (ref "Q202")
      (value "BC817")
      (footprint "eagle-import:SOT23")
      (libsource (lib "eagle-import") (part "BC817"))
    )
    (comp (ref "R201")
      (value "2M")
      (footprint "eagle-import:RESC3216")
      (libsource (lib "eagle-import") (part "R-EU-3216"))
    )
    (comp (ref "R202")
      (value "2k15")
      (footprint "eagle-import:RESC2012")
      (libsource (lib "eagle-import") (part "R-EU-2012"))
    )
    (comp (ref "R203")
      (value "2M")
      (footprint "eagle-import:RESC3216")
      (libsource (lib "eagle-import") (part "R-EU-3216"))
    )
    (comp (ref "R204")
      (value "2M")
      (footprint "eagle-import:RESC3216")
      (libsource (lib "eagle-import") (part "R-EU-3216"))
    )
    (comp (ref "R205")
      (value "2M")
      (footprint "eagle-import:RESC3216")
      (libsource (lib "eagle-import") (part "R-EU-3216"))
    )
    (comp (ref "R206")
      (value "2M")
      (footprint "eagle-import:RESC3216")
      (libsource (lib "eagle-import") (part "R-EU-3216"))
    )
    (comp (ref "R207")
      (value "2k15")
      (footprint "eagle-import:RESC2012")
      (libsource (lib "eagle-import") (part "R-EU-2012"))
    )
    (comp (ref "R208")
      (value "2k15")
      (footprint "eagle-import:RESC2012")
      (libsource (lib "eagle-import") (part "R-EU-2012"))
    )
    (comp (ref "R209")
      (value "100R")
      (footprint "eagle-import:RESC1608")
      (libsource (lib "eagle-import") (part "R-EU-1608"))
    )
    (comp (ref "R210")
      (value "10k")
      (footprint "eagle-import:RESC1608")
      (libsource (lib "eagle-import") (part "R-EU-1608"))
    )
    (comp (ref "R211")
      (value "350R")
      (footprint "eagle-import:RESC1608")
      (libsource (lib "eagle-import") (part "R-EU-1608"))
    )
    (comp (ref "R212")
      (value "350R")
      (footprint "eagle-import:RESC1608")
      (libsource (lib "eagle-import") (part "R-EU-1608"))
    )
    (comp (ref "SJ201")
      (value "DUT_GND")
      (footprint "eagle-import:SJW")
      (libsource (lib "eagle-import") (part "SJW"))
    )
    (comp (ref "U201")
      (value "LP2985-3.1")
      (footprint "eagle-import:SOT23-5L")
      (libsource (lib "eagle-import") (part "LP2985-3.1"))
    )
    (comp (ref "U202")
      (value "LP2985-3.1")
      (footprint "eagle-import:SOT23-5L")
      (libsource (lib "eagle-import") (part "LP2985-3.1"))
    )
    (comp (ref "U203")
      (value "LP2985-3.1")
      (footprint "eagle-import:SOT23-5L")
      (libsource (lib "eagle-import") (part "LP2985-3.1"))
    )
    (comp (ref "U204")
      (value "AD620")
      (footprint "eagle-import:SO8")
      (libsource (lib "eagle-import") (part "AD620R-8"))
    )
    (comp (ref "U205")
      (value "78L05_TO-220AB-3-BR")
      (footprint "eagle-import:TO-220AB-3-BR")
      (libsource (lib "eagle-import") (part "78L05_TO-220AB-3-BR"))
    )
    (comp (ref "U207")
      (value "LTC1865L")
      (footprint "eagle-import:SO8")
      (libsource (lib "eagle-import") (part "LTC1865L"))
    )
    (comp (ref "U208")
      (value "LTC1865L")
      (footprint "eagle-import:SO8")
      (libsource (lib "eagle-import") (part "LTC1865L"))
    )
    (comp (ref "U209")
      (value "MAX743")
      (footprint "eagle-import:SO16W")
      (libsource (lib "eagle-import") (part "MAX743WE"))
    )
  )
  (nets
    (net (code "1") (name "+3V3") (class "Default")
      (node (ref "C210") (pin "1") (pinfunction "1_1") (pintype "passive"))
      (node (ref "R310") (pin "2") (pinfunction "2_2") (pintype "passive"))
      (node (ref "R311") (pin "2") (pinfunction "2_2") (pintype "passive"))
      (node (ref "R312") (pin "2") (pinfunction "2_2") (pintype "passive"))
      (node (ref "R314") (pin "2") (pinfunction "2_2") (pintype "passive"))
      (node (ref "R315") (pin "2") (pinfunction "2_2") (pintype "passive"))
      (node (ref "R316") (pin "2") (pinfunction "2_2") (pintype "passive"))
      (node (ref "U203") (pin "5") (pinfunction "VOUT_5") (pintype "power_in"))
    )
    (net (code "2") (name "+3V_1") (class "Default")
      (node (ref "C133") (pin "1") (pinfunction "1_1") (pintype "passive"))
      (node (ref "C135") (pin "1") (pinfunction "1_1") (pintype "passive"))
      (node (ref "C208") (pin "1") (pinfunction "1_1") (pintype "passive"))
      (node (ref "C217") (pin "1") (pinfunction "1_1") (pintype "passive"))
      (node (ref "C220") (pin "1") (pinfunction "1_1") (pintype "passive"))
      (node (ref "D101") (pin "2") (pinfunction "C2_2") (pintype "passive"))
      (node (ref "D102") (pin "2") (pinfunction "C2_2") (pintype "passive"))
      (node (ref "U109") (pin "8") (pinfunction "VCC_8") (pintype "power_in"))
      (node (ref "U201") (pin "5") (pinfunction "VOUT_5") (pintype "power_in"))
      (node (ref "U207") (pin "8") (pinfunction "VCC_8") (pintype "power_in"))
    )
    (net (code "3") (name "+3V_2") (class "Default")
      (node (ref "C134") (pin "1") (pinfunction "1_1") (pintype "passive"))
      (node (ref "C136") (pin "1") (pinfunction "1_1") (pintype "passive"))
      (node (ref "C209") (pin "1") (pinfunction "1_1") (pintype "passive"))
      (node (ref "C224") (pin "1") (pinfunction "1_1") (pintype "passive"))
      (node (ref "C228") (pin "1") (pinfunction "1_1") (pintype "passive"))
      (node (ref "D103") (pin "2") (pinfunction "C2_2") (pintype "passive"))
      (node (ref "D104") (pin "2") (pinfunction "C2_2") (pintype "passive"))
      (node (ref "D201") (pin "2") (pinfunction "C2_2") (pintype "passive"))
      (node (ref "U110") (pin "8") (pinfunction "VCC_8") (pintype "power_in"))
      (node (ref "U202") (pin "5") (pinfunction "VOUT_5") (pintype "power_in"))
      (node (ref "U208") (pin "8") (pinfunction "VCC_8") (pintype "power_in"))
    )
    (net (code "4") (name "+5V") (class "Default")
      (node (ref "C101") (pin "1") (pinfunction "1_1") (pintype "passive"))
      (node (ref "C102") (pin "1") (pinfunction "1_1") (pintype "passive"))
      (node (ref "C103") (pin "1") (pinfunction "1_1") (pintype "passive"))
      (node (ref "C104") (pin "1") (pinfunction "1_1") (pintype "passive"))
      (node (ref "C203") (pin "1") (pinfunction "1_1") (pintype "passive"))
      (node (ref "C204") (pin "1") (pinfunction "1_1") (pintype "passive"))
      (node (ref "C214") (pin "1") (pinfunction "1_1") (pintype "passive"))
      (node (ref "C221") (pin "1") (pinfunction "1_1") (pintype "passive"))
      (node (ref "C223") (pin "+") (pinfunction "+_+") (pintype "passive"))
      (node (ref "C225") (pin "1") (pinfunction "1_1") (pintype "passive"))
      (node (ref "C229") (pin "2") (pinfunction "2_2") (pintype "passive"))
      (node (ref "C301") (pin "1") (pinfunction "1_1") (pintype "passive"))
      (node (ref "C302") (pin "1") (pinfunction "1_1") (pintype "passive"))
      (node (ref "C303") (pin "1") (pinfunction "1_1") (pintype "passive"))
      (node (ref "C304") (pin "1") (pinfunction "1_1") (pintype "passive"))
      (node (ref "C305") (pin "1") (pinfunction "1_1") (pintype "passive"))
      (node (ref "C306") (pin "1") (pinfunction "1_1") (pintype "passive"))
      (node (ref "C307") (pin "1") (pinfunction "1_1") (pintype "passive"))
      (node (ref "C308") (pin "1") (pinfunction "1_1") (pintype "passive"))
      (node (ref "C317") (pin "1") (pinfunction "1_1") (pintype "passive"))
      (node (ref "C318") (pin "1") (pinfunction "1_1") (pintype "passive"))
      (node (ref "C320") (pin "1") (pinfunction "1_1") (pintype "passive"))
      (node (ref "C321") (pin "1") (pinfunction "1_1") (pintype "passive"))
      (node (ref "J201") (pin "3") (pinfunction "3_3") (pintype "passive"))
      (node (ref "J201") (pin "4") (pinfunction "4_4") (pintype "passive"))
      (node (ref "L201") (pin "1") (pinfunction "1_1") (pintype "passive"))
      (node (ref "R1") (pin "2") (pinfunction "2_2") (pintype "passive"))
      (node (ref "R309") (pin "2") (pinfunction "2_2") (pintype "passive"))
      (node (ref "R313") (pin "2") (pinfunction "2_2") (pintype "passive"))
      (node (ref "R319") (pin "2") (pinfunction "2_2") (pintype "passive"))
      (node (ref "R322") (pin "2") (pinfunction "2_2") (pintype "passive"))
      (node (ref "R323") (pin "2") (pinfunction "2_2") (pintype "passive"))
      (node (ref "R324") (pin "2") (pinfunction "2_2") (pintype "passive"))
      (node (ref "R326") (pin "2") (pinfunction "2_2") (pintype "passive"))
      (node (ref "R327") (pin "2") (pinfunction "2_2") (pintype "passive"))
      (node (ref "U101") (pin "2") (pinfunction "VLL_2") (pintype "bidirectional"))
      (node (ref "U102") (pin "2") (pinfunction "VLL_2") (pintype "bidirectional"))
      (node (ref "U203") (pin "1") (pinfunction "VIN_1") (pintype "power_in"))
      (node (ref "U203") (pin "3") (pinfunction "ON/OFF_3") (pintype "input"))
      (node (ref "U205") (pin "3") (pinfunction "VO_3") (pintype "passive"))
      (node (ref "U209") (pin "12") (pinfunction "V+_12") (pintype "input"))
      (node (ref "U209") (pin "13") (pinfunction "V+_13") (pintype "input"))
      (node (ref "U209") (pin "3") (pinfunction "AV+_3") (pintype "input"))
      (node (ref "U209") (pin "4") (pinfunction "V+_4") (pintype "input"))
      (node (ref "U209") (pin "5") (pinfunction "V+_5") (pintype "input"))
      (node (ref "U301") (pin "8") (pinfunction "VCC_8") (pintype "power_in"))
      (node (ref "U302") (pin "8") (pinfunction "VCC_8") (pintype "power_in"))
      (node (ref "U303") (pin "8") (pinfunction "VCC_8") (pintype "power_in"))
      (node (ref "U304") (pin "8") (pinfunction "VCC_8") (pintype "power_in"))
      (node (ref "U305") (pin "8") (pinfunction "VCC_8") (pintype "power_in"))
      (node (ref "U306") (pin "8") (pinfunction "VCC_8") (pintype "power_in"))
    )
    (net (code "5") (name "+5V_I") (class "Default")
      (node (ref "C319") (pin "1") (pinfunction "1_1") (pintype "passive"))
      (node (ref "C322") (pin "1") (pinfunction "1_1") (pintype "passive"))
      (node (ref "J203") (pin "16") (pinfunction "16_16") (pintype "passive"))
      (node (ref "R301") (pin "2") (pinfunction "2_2") (pintype "passive"))
      (node (ref "R302") (pin "2") (pinfunction "2_2") (pintype "passive"))
      (node (ref "R303") (pin "2") (pinfunction "2_2") (pintype "passive"))
      (node (ref "R304") (pin "2") (pinfunction "2_2") (pintype "passive"))
      (node (ref "R305") (pin "2") (pinfunction "2_2") (pintype "passive"))
      (node (ref "R306") (pin "2") (pinfunction "2_2") (pintype "passive"))
      (node (ref "R307") (pin "2") (pinfunction "2_2") (pintype "passive"))
      (node (ref "R308") (pin "2") (pinfunction "2_2") (pintype "passive"))
      (node (ref "R317") (pin "2") (pinfunction "2_2") (pintype "passive"))
      (node (ref "R318") (pin "2") (pinfunction "2_2") (pintype "passive"))
      (node (ref "R320") (pin "2") (pinfunction "2_2") (pintype "passive"))
      (node (ref "R321") (pin "2") (pinfunction "2_2") (pintype "passive"))
      (node (ref "R325") (pin "2") (pinfunction "2_2") (pintype "passive"))
      (node (ref "R328") (pin "2") (pinfunction "2_2") (pintype "passive"))
      (node (ref "U307") (pin "8") (pinfunction "VCC_8") (pintype "power_in"))
    )
    (net (code "6") (name "+12V") (class "Default")
      (node (ref "C105") (pin "1") (pinfunction "1_1") (pintype "passive"))
      (node (ref "C106") (pin "1") (pinfunction "1_1") (pintype "passive"))
      (node (ref "C107") (pin "1") (pinfunction "1_1") (pintype "passive"))
      (node (ref "C108") (pin "1") (pinfunction "1_1") (pintype "passive"))
      (node (ref "C109") (pin "1") (pinfunction "1_1") (pintype "passive"))
      (node (ref "C110") (pin "1") (pinfunction "1_1") (pintype "passive"))
      (node (ref "C119") (pin "1") (pinfunction "1_1") (pintype "passive"))
      (node (ref "C120") (pin "1") (pinfunction "1_1") (pintype "passive"))
      (node (ref "C212") (pin "1") (pinfunction "1_1") (pintype "passive"))
      (node (ref "C232") (pin "+") (pinfunction "+_+") (pintype "passive"))
      (node (ref "J202") (pin "3") (pinfunction "3_3") (pintype "passive"))
      (node (ref "J204") (pin "2") (pinfunction "+12V_2") (pintype "passive"))
      (node (ref "J205") (pin "2") (pinfunction "+12V_2") (pintype "passive"))
      (node (ref "Q115") (pin "3") (pinfunction "C_3") (pintype "passive"))
      (node (ref "Q117") (pin "3") (pinfunction "C_3") (pintype "passive"))
      (node (ref "R115") (pin "2") (pinfunction "2_2") (pintype "passive"))
      (node (ref "R116") (pin "2") (pinfunction "2_2") (pintype "passive"))
      (node (ref "R117") (pin "2") (pinfunction "2_2") (pintype "passive"))
      (node (ref "R119") (pin "2") (pinfunction "2_2") (pintype "passive"))
      (node (ref "U101") (pin "23") (pinfunction "VCC_23") (pintype "bidirectional"))
      (node (ref "U102") (pin "23") (pinfunction "VCC_23") (pintype "bidirectional"))
      (node (ref "U205") (pin "1") (pinfunction "VI_1") (pintype "input"))
    )
    (net (code "7") (name "+15V") (class "Default")
      (node (ref "C111") (pin "1") (pinfunction "1_1") (pintype "passive"))
      (node (ref "C113") (pin "1") (pinfunction "1_1") (pintype "passive"))
      (node (ref "C115") (pin "1") (pinfunction "1_1") (pintype "passive"))
      (node (ref "C117") (pin "1") (pinfunction "1_1") (pintype "passive"))
      (node (ref "C121") (pin "1") (pinfunction "1_1") (pintype "passive"))
      (node (ref "C122") (pin "1") (pinfunction "1_1") (pintype "passive"))
      (node (ref "C123") (pin "1") (pinfunction "1_1") (pintype "passive"))
      (node (ref "C124") (pin "1") (pinfunction "1_1") (pintype "passive"))
      (node (ref "C216") (pin "1") (pinfunction "1_1") (pintype "passive"))
      (node (ref "Q102") (pin "3") (pinfunction "C_3") (pintype "passive"))
      (node (ref "Q104") (pin "3") (pinfunction "C_3") (pintype "passive"))
      (node (ref "Q105") (pin "3") (pinfunction "C_3") (pintype "passive"))
      (node (ref "Q107") (pin "3") (pinfunction "C_3") (pintype "passive"))
      (node (ref "Q202") (pin "2") (pinfunction "E_2") (pintype "passive"))
      (node (ref "R103") (pin "2") (pinfunction "2_2") (pintype "passive"))
      (node (ref "R105") (pin "2") (pinfunction "2_2") (pintype "passive"))
      (node (ref "U103") (pin "7") (pinfunction "+V_7") (pintype "power_in"))
      (node (ref "U104") (pin "7") (pinfunction "+V_7") (pintype "power_in"))
      (node (ref "U105") (pin "7") (pinfunction "+V_7") (pintype "power_in"))
      (node (ref "U106") (pin "7") (pinfunction "+V_7") (pintype "power_in"))
      (node (ref "U107") (pin "7") (pinfunction "+V_7") (pintype "power_in"))
      (node (ref "U108") (pin "7") (pinfunction "+V_7") (pintype "power_in"))
      (node (ref "U204") (pin "7") (pinfunction "+V_7") (pintype "power_in"))
    )
    (net (code "8") (name "-15V") (class "Default")
      (node (ref "C112") (pin "2") (pinfunction "2_2") (pintype "passive"))
      (node (ref "C114") (pin "2") (pinfunction "2_2") (pintype "passive"))
      (node (ref "C116") (pin "2") (pinfunction "2_2") (pintype "passive"))
      (node (ref "C118") (pin "2") (pinfunction "2_2") (pintype "passive"))
      (node (ref "C125") (pin "1") (pinfunction "1_1") (pintype "passive"))
      (node (ref "C126") (pin "1") (pinfunction "1_1") (pintype "passive"))
      (node (ref "C127") (pin "1") (pinfunction "1_1") (pintype "passive"))
      (node (ref "C128") (pin "1") (pinfunction "1_1") (pintype "passive"))
      (node (ref "C219") (pin "1") (pinfunction "1_1") (pintype "passive"))
      (node (ref "Q101") (pin "3") (pinfunction "C_3") (pintype "passive"))
      (node (ref "Q103") (pin "3") (pinfunction "C_3") (pintype "passive"))
      (node (ref "Q106") (pin "3") (pinfunction "C_3") (pintype "passive"))
      (node (ref "Q108") (pin "3") (pinfunction "C_3") (pintype "passive"))
      (node (ref "Q201") (pin "2") (pinfunction "E_2") (pintype "passive"))
      (node (ref "R104") (pin "1") (pinfunction "1_1") (pintype "passive"))
      (node (ref "R106") (pin "1") (pinfunction "1_1") (pintype "passive"))
      (node (ref "U103") (pin "4") (pinfunction "-V_4") (pintype "power_in"))
      (node (ref "U104") (pin "4") (pinfunction "-V_4") (pintype "power_in"))
      (node (ref "U105") (pin "4") (pinfunction "-V_4") (pintype "power_in"))
      (node (ref "U106") (pin "4") (pinfunction "-V_4") (pintype "power_in"))
      (node (ref "U107") (pin "4") (pinfunction "-V_4") (pintype "power_in"))
      (node (ref "U108") (pin "4") (pinfunction "-V_4") (pintype "power_in"))
      (node (ref "U204") (pin "4") (pinfunction "-V_4") (pintype "power_in"))
    )
    (net (code "9") (name "BYP") (class "Default")
      (node (ref "C309") (pin "1") (pinfunction "1_1") (pintype "passive"))
      (node (ref "R111") (pin "1") (pinfunction "1_1") (pintype "passive"))
      (node (ref "R113") (pin "1") (pinfunction "1_1") (pintype "passive"))
      (node (ref "R309") (pin "1") (pinfunction "1_1") (pintype "passive"))
      (node (ref "U301") (pin "7") (pinfunction "VO1_7") (pintype "output"))
    )
    (net (code "10") (name "BYP_I") (class "Default")
      (node (ref "J203") (pin "8") (pinfunction "8_8") (pintype "passive"))
      (node (ref "Q301") (pin "1") (pinfunction "B_1") (pintype "passive"))
    )
    (net (code "11") (name "CLR_DAC1") (class "Default")
      (node (ref "C324") (pin "1") (pinfunction "1_1") (pintype "passive"))
      (node (ref "R324") (pin "1") (pinfunction "1_1") (pintype "passive"))
      (node (ref "U101") (pin "6") (pinfunction "CLR_6") (pintype "bidirectional"))
      (node (ref "U306") (pin "7") (pinfunction "VO1_7") (pintype "output"))
    )
    (net (code "12") (name "CLR_DAC1_I") (class "Default")
      (node (ref "J203") (pin "6") (pinfunction "6_6") (pintype "passive"))
      (node (ref "Q310") (pin "1") (pinfunction "B_1") (pintype "passive"))
    )
    (net (code "13") (name "CLR_DAC2") (class "Default")
      (node (ref "C313") (pin "1") (pinfunction "1_1") (pintype "passive"))
      (node (ref "R313") (pin "1") (pinfunction "1_1") (pintype "passive"))
      (node (ref "U102") (pin "6") (pinfunction "CLR_6") (pintype "bidirectional"))
      (node (ref "U301") (pin "6") (pinfunction "VO2_6") (pintype "output"))
    )
    (net (code "14") (name "CLR_DAC2_I") (class "Default")
      (node (ref "J203") (pin "7") (pinfunction "7_7") (pintype "passive"))
      (node (ref "Q305") (pin "1") (pinfunction "B_1") (pintype "passive"))
    )
    (net (code "15") (name "CONV_C1") (class "Default")
      (node (ref "C315") (pin "1") (pinfunction "1_1") (pintype "passive"))
      (node (ref "R315") (pin "1") (pinfunction "1_1") (pintype "passive"))
      (node (ref "U109") (pin "1") (pinfunction "CONV_1") (pintype "input"))
      (node (ref "U303") (pin "6") (pinfunction "VO2_6") (pintype "output"))
    )
    (net (code "16") (name "CONV_C1_I") (class "Default")
      (node (ref "J203") (pin "9") (pinfunction "9_9") (pintype "passive"))
      (node (ref "Q307") (pin "1") (pinfunction "B_1") (pintype "passive"))
    )
    (net (code "17") (name "CONV_C2") (class "Default")
      (node (ref "C316") (pin "1") (pinfunction "1_1") (pintype "passive"))
      (node (ref "R316") (pin "1") (pinfunction "1_1") (pintype "passive"))
      (node (ref "U110") (pin "1") (pinfunction "CONV_1") (pintype "input"))
      (node (ref "U304") (pin "6") (pinfunction "VO2_6") (pintype "output"))
    )
    (net (code "18") (name "CONV_C2_I") (class "Default")
      (node (ref "J203") (pin "11") (pinfunction "11_11") (pintype "passive"))
      (node (ref "Q308") (pin "1") (pinfunction "B_1") (pintype "passive"))
    )
    (net (code "19") (name "CONV_TEMP") (class "Default")
      (node (ref "C311") (pin "1") (pinfunction "1_1") (pintype "passive"))
      (node (ref "R311") (pin "1") (pinfunction "1_1") (pintype "passive"))
      (node (ref "U207") (pin "1") (pinfunction "CONV_1") (pintype "input"))
      (node (ref "U303") (pin "7") (pinfunction "VO1_7") (pintype "output"))
    )
    (net (code "20") (name "CONV_TEMP_I") (class "Default")
      (node (ref "J203") (pin "10") (pinfunction "10_10") (pintype "passive"))
      (node (ref "Q303") (pin "1") (pinfunction "B_1") (pintype "passive"))
    )
    (net (code "21") (name "CONV_V") (class "Default")
      (node (ref "C312") (pin "1") (pinfunction "1_1") (pintype "passive"))
      (node (ref "R312") (pin "1") (pinfunction "1_1") (pintype "passive"))
      (node (ref "U208") (pin "1") (pinfunction "CONV_1") (pintype "input"))
      (node (ref "U304") (pin "7") (pinfunction "VO1_7") (pintype "output"))
    )
    (net (code "22") (name "CONV_V_I") (class "Default")
      (node (ref "J203") (pin "12") (pinfunction "12_12") (pintype "passive"))
      (node (ref "Q304") (pin "1") (pinfunction "B_1") (pintype "passive"))
    )
    (net (code "23") (name "CSEN_H1") (class "Default")
      (node (ref "Q109") (pin "1") (pinfunction "S_1") (pintype "passive"))
      (node (ref "Q109") (pin "2") (pinfunction "S_2") (pintype "passive"))
      (node (ref "Q109") (pin "3") (pinfunction "S_3") (pintype "passive"))
      (node (ref "Q113") (pin "1") (pinfunction "S_1") (pintype "passive"))
      (node (ref "Q113") (pin "2") (pinfunction "S_2") (pintype "passive"))
      (node (ref "Q113") (pin "3") (pinfunction "S_3") (pintype "passive"))
      (node (ref "R121") (pin "2") (pinfunction "2_2") (pintype "passive"))
      (node (ref "R123") (pin "1") (pinfunction "1_1") (pintype "passive"))
      (node (ref "R124") (pin "2") (pinfunction "2_2") (pintype "passive"))
      (node (ref "R128") (pin "2") (pinfunction "2_2") (pintype "passive"))
      (node (ref "R129") (pin "2") (pinfunction "2_2") (pintype "passive"))
      (node (ref "U105") (pin "3") (pinfunction "+_3") (pintype "input"))
      (node (ref "U106") (pin "2") (pinfunction "-_2") (pintype "input"))
    )
    (net (code "24") (name "CSEN_H2") (class "Default")
      (node (ref "Q110") (pin "1") (pinfunction "S_1") (pintype "passive"))
      (node (ref "Q110") (pin "2") (pinfunction "S_2") (pintype "passive"))
      (node (ref "Q110") (pin "3") (pinfunction "S_3") (pintype "passive"))
      (node (ref "Q114") (pin "1") (pinfunction "S_1") (pintype "passive"))
      (node (ref "Q114") (pin "2") (pinfunction "S_2") (pintype "passive"))
      (node (ref "Q114") (pin "3") (pinfunction "S_3") (pintype "passive"))
      (node (ref "R122") (pin "2") (pinfunction "2_2") (pintype "passive"))
      (node (ref "R125") (pin "1") (pinfunction "1_1") (pintype "passive"))
      (node (ref "R126") (pin "2") (pinfunction "2_2") (pintype "passive"))
      (node (ref "R127") (pin "1") (pinfunction "1_1") (pintype "passive"))
      (node (ref "R130") (pin "2") (pinfunction "2_2") (pintype "passive"))
      (node (ref "U107") (pin "3") (pinfunction "+_3") (pintype "input"))
      (node (ref "U108") (pin "2") (pinfunction "-_2") (pintype "input"))
    )
    (net (code "25") (name "CSEN_L1") (class "Default")
      (node (ref "Q109") (pin "5") (pinfunction "D_5") (pintype "passive"))
      (node (ref "Q109") (pin "6") (pinfunction "D_6") (pintype "passive"))
      (node (ref "Q109") (pin "7") (pinfunction "D_7") (pintype "passive"))
      (node (ref "Q109") (pin "8") (pinfunction "D_8") (pintype "passive"))
      (node (ref "Q113") (pin "5") (pinfunction "D_5") (pintype "passive"))
      (node (ref "Q113") (pin "6") (pinfunction "D_6") (pintype "passive"))
      (node (ref "Q113") (pin "7") (pinfunction "D_7") (pintype "passive"))
      (node (ref "Q113") (pin "8") (pinfunction "D_8") (pintype "passive"))
      (node (ref "Q119") (pin "1") (pinfunction "S_1") (pintype "passive"))
      (node (ref "R123") (pin "2") (pinfunction "2_2") (pintype "passive"))
      (node (ref "U103") (pin "5") (pinfunction "REF_5") (pintype "passive"))
      (node (ref "U106") (pin "3") (pinfunction "+_3") (pintype "input"))
    )
    (net (code "26") (name "CSEN_L2") (class "Default")
      (node (ref "Q110") (pin "5") (pinfunction "D_5") (pintype "passive"))
      (node (ref "Q110") (pin "6") (pinfunction "D_6") (pintype "passive"))
      (node (ref "Q110") (pin "7") (pinfunction "D_7") (pintype "passive"))
      (node (ref "Q110") (pin "8") (pinfunction "D_8") (pintype "passive"))
      (node (ref "Q114") (pin "5") (pinfunction "D_5") (pintype "passive"))
      (node (ref "Q114") (pin "6") (pinfunction "D_6") (pintype "passive"))
      (node (ref "Q114") (pin "7") (pinfunction "D_7") (pintype "passive"))
      (node (ref "Q114") (pin "8") (pinfunction "D_8") (pintype "passive"))
      (node (ref "Q120") (pin "1") (pinfunction "S_1") (pintype "passive"))
      (node (ref "R125") (pin "2") (pinfunction "2_2") (pintype "passive"))
      (node (ref "U104") (pin "5") (pinfunction "REF_5") (pintype "passive"))
      (node (ref "U108") (pin "3") (pinfunction "+_3") (pintype "input"))
    )
    (net (code "27") (name "DUT+") (class "Default")
      (node (ref "J206") (pin "2") (pinfunction "1_2") (pintype "passive"))
      (node (ref "Q119") (pin "2") (pinfunction "D_2") (pintype "passive"))
      (node (ref "Q120") (pin "2") (pinfunction "D_2") (pintype "passive"))
    )
    (net (code "28") (name "DUT-") (class "Default")
      (node (ref "J207") (pin "1") (pinfunction "1_1") (pintype "passive"))
      (node (ref "R121") (pin "1") (pinfunction "1_1") (pintype "passive"))
      (node (ref "R122") (pin "1") (pinfunction "1_1") (pintype "passive"))
      (node (ref "R124") (pin "1") (pinfunction "1_1") (pintype "passive"))
      (node (ref "R126") (pin "1") (pinfunction "1_1") (pintype "passive"))
      (node (ref "R129") (pin "1") (pinfunction "1_1") (pintype "passive"))
      (node (ref "R130") (pin "1") (pinfunction "1_1") (pintype "passive"))
      (node (ref "SJ201") (pin "2") (pinfunction "2_2") (pintype "passive"))
      (node (ref "U105") (pin "2") (pinfunction "-_2") (pintype "input"))
      (node (ref "U107") (pin "2") (pinfunction "-_2") (pintype "input"))
    )
    (net (code "29") (name "FAN1_PWM") (class "Default")
      (node (ref "C323") (pin "1") (pinfunction "1_1") (pintype "passive"))
      (node (ref "J204") (pin "4") (pinfunction "PWM_4") (pintype "passive"))
      (node (ref "R323") (pin "1") (pinfunction "1_1") (pintype "passive"))
      (node (ref "U305") (pin "7") (pinfunction "VO1_7") (pintype "output"))
    )
    (net (code "30") (name "FAN1_PWM_I") (class "Default")
      (node (ref "J203") (pin "14") (pinfunction "14_14") (pintype "passive"))
      (node (ref "Q309") (pin "1") (pinfunction "B_1") (pintype "passive"))
    )
    (net (code "31") (name "FAN1_SIG") (class "Default")
      (node (ref "J204") (pin "3") (pinfunction "SIG_3") (pintype "passive"))
    )
    (net (code "32") (name "FAN2_PWM") (class "Default")
      (node (ref "C326") (pin "1") (pinfunction "1_1") (pintype "passive"))
      (node (ref "J205") (pin "4") (pinfunction "PWM_4") (pintype "passive"))
      (node (ref "R326") (pin "1") (pinfunction "1_1") (pintype "passive"))
      (node (ref "U305") (pin "6") (pinfunction "VO2_6") (pintype "output"))
    )
    (net (code "33") (name "FAN2_PWM_I") (class "Default")
      (node (ref "J203") (pin "13") (pinfunction "13_13") (pintype "passive"))
      (node (ref "Q312") (pin "1") (pinfunction "B_1") (pintype "passive"))
    )
    (net (code "34") (name "FAN2_SIG") (class "Default")
      (node (ref "J205") (pin "3") (pinfunction "SIG_3") (pintype "passive"))
    )
    (net (code "35") (name "FLT_DAC") (class "Default")
      (node (ref "Q311") (pin "1") (pinfunction "B_1") (pintype "passive"))
      (node (ref "U101") (pin "3") (pinfunction "FLT_3") (pintype "bidirectional"))
      (node (ref "U102") (pin "3") (pinfunction "FLT_3") (pintype "bidirectional"))
    )
    (net (code "36") (name "FLT_DAC_I") (class "Default")
      (node (ref "C325") (pin "1") (pinfunction "1_1") (pintype "passive"))
      (node (ref "J203") (pin "1") (pinfunction "1_1") (pintype "passive"))
      (node (ref "R325") (pin "1") (pinfunction "1_1") (pintype "passive"))
      (node (ref "U307") (pin "7") (pinfunction "VO1_7") (pintype "output"))
    )
    (net (code "37") (name "GND") (class "Default")
      (node (ref "C101") (pin "2") (pinfunction "2_2") (pintype "passive"))
      (node (ref "C102") (pin "2") (pinfunction "2_2") (pintype "passive"))
      (node (ref "C103") (pin "2") (pinfunction "2_2") (pintype "passive"))
      (node (ref "C104") (pin "2") (pinfunction "2_2") (pintype "passive"))
      (node (ref "C105") (pin "2") (pinfunction "2_2") (pintype "passive"))
      (node (ref "C106") (pin "2") (pinfunction "2_2") (pintype "passive"))
      (node (ref "C111") (pin "2") (pinfunction "2_2") (pintype "passive"))
      (node (ref "C112") (pin "1") (pinfunction "1_1") (pintype "passive"))
      (node (ref "C113") (pin "2") (pinfunction "2_2") (pintype "passive"))
      (node (ref "C114") (pin "1") (pinfunction "1_1") (pintype "passive"))
      (node (ref "C115") (pin "2") (pinfunction "2_2") (pintype "passive"))
      (node (ref "C116") (pin "1") (pinfunction "1_1") (pintype "passive"))
      (node (ref "C117") (pin "2") (pinfunction "2_2") (pintype "passive"))
      (node (ref "C118") (pin "1") (pinfunction "1_1") (pintype "passive"))
      (node (ref "C119") (pin "2") (pinfunction "2_2") (pintype "passive"))
      (node (ref "C120") (pin "2") (pinfunction "2_2") (pintype "passive"))
      (node (ref "C121") (pin "2") (pinfunction "2_2") (pintype "passive"))
      (node (ref "C122") (pin "2") (pinfunction "2_2") (pintype "passive"))
      (node (ref "C123") (pin "2") (pinfunction "2_2") (pintype "passive"))
      (node (ref "C124") (pin "2") (pinfunction "2_2") (pintype "passive"))
      (node (ref "C125") (pin "2") (pinfunction "2_2") (pintype "passive"))
      (node (ref "C126") (pin "2") (pinfunction "2_2") (pintype "passive"))
      (node (ref "C127") (pin "2") (pinfunction "2_2") (pintype "passive"))
      (node (ref "C128") (pin "2") (pinfunction "2_2") (pintype "passive"))
      (node (ref "C129") (pin "2") (pinfunction "2_2") (pintype "passive"))
      (node (ref "C130") (pin "2") (pinfunction "2_2") (pintype "passive"))
      (node (ref "C131") (pin "2") (pinfunction "2_2") (pintype "passive"))
      (node (ref "C132") (pin "2") (pinfunction "2_2") (pintype "passive"))
      (node (ref "C133") (pin "2") (pinfunction "2_2") (pintype "passive"))
      (node (ref "C134") (pin "2") (pinfunction "2_2") (pintype "passive"))
      (node (ref "C135") (pin "2") (pinfunction "2_2") (pintype "passive"))
      (node (ref "C136") (pin "2") (pinfunction "2_2") (pintype "passive"))
      (node (ref "C201") (pin "2") (pinfunction "2_2") (pintype "passive"))
      (node (ref "C202") (pin "2") (pinfunction "2_2") (pintype "passive"))
      (node (ref "C203") (pin "2") (pinfunction "2_2") (pintype "passive"))
      (node (ref "C204") (pin "2") (pinfunction "2_2") (pintype "passive"))
      (node (ref "C205") (pin "2") (pinfunction "2_2") (pintype "passive"))
      (node (ref "C206") (pin "2") (pinfunction "2_2") (pintype "passive"))
      (node (ref "C207") (pin "2") (pinfunction "2_2") (pintype "passive"))
      (node (ref "C208") (pin "2") (pinfunction "2_2") (pintype "passive"))
      (node (ref "C209") (pin "2") (pinfunction "2_2") (pintype "passive"))
      (node (ref "C210") (pin "2") (pinfunction "2_2") (pintype "passive"))
      (node (ref "C211") (pin "2") (pinfunction "2_2") (pintype "passive"))
      (node (ref "C212") (pin "2") (pinfunction "2_2") (pintype "passive"))
      (node (ref "C214") (pin "2") (pinfunction "2_2") (pintype "passive"))
      (node (ref "C215") (pin "2") (pinfunction "2_2") (pintype "passive"))
      (node (ref "C216") (pin "2") (pinfunction "2_2") (pintype "passive"))
      (node (ref "C217") (pin "2") (pinfunction "2_2") (pintype "passive"))
      (node (ref "C218") (pin "2") (pinfunction "2_2") (pintype "passive"))
      (node (ref "C219") (pin "2") (pinfunction "2_2") (pintype "passive"))
      (node (ref "C220") (pin "2") (pinfunction "2_2") (pintype "passive"))
      (node (ref "C221") (pin "2") (pinfunction "2_2") (pintype "passive"))
      (node (ref "C223") (pin "-") (pinfunction "-_-") (pintype "passive"))
      (node (ref "C224") (pin "2") (pinfunction "2_2") (pintype "passive"))
      (node (ref "C225") (pin "2") (pinfunction "2_2") (pintype "passive"))
      (node (ref "C226") (pin "1") (pinfunction "1_1") (pintype "passive"))
      (node (ref "C227") (pin "-") (pinfunction "-_-") (pintype "passive"))
      (node (ref "C228") (pin "2") (pinfunction "2_2") (pintype "passive"))
      (node (ref "C229") (pin "1") (pinfunction "1_1") (pintype "passive"))
      (node (ref "C230") (pin "2") (pinfunction "2_2") (pintype "passive"))
      (node (ref "C231") (pin "2") (pinfunction "2_2") (pintype "passive"))
      (node (ref "C232") (pin "-") (pinfunction "-_-") (pintype "passive"))
      (node (ref "C234") (pin "-") (pinfunction "-_-") (pintype "passive"))
      (node (ref "C235") (pin "+") (pinfunction "+_+") (pintype "passive"))
      (node (ref "C237") (pin "2") (pinfunction "2_2") (pintype "passive"))
      (node (ref "C238") (pin "2") (pinfunction "2_2") (pintype "passive"))
      (node (ref "C301") (pin "2") (pinfunction "2_2") (pintype "passive"))
      (node (ref "C302") (pin "2") (pinfunction "2_2") (pintype "passive"))
      (node (ref "C303") (pin "2") (pinfunction "2_2") (pintype "passive"))
      (node (ref "C304") (pin "2") (pinfunction "2_2") (pintype "passive"))
      (node (ref "C305") (pin "2") (pinfunction "2_2") (pintype "passive"))
      (node (ref "C306") (pin "2") (pinfunction "2_2") (pintype "passive"))
      (node (ref "C307") (pin "2") (pinfunction "2_2") (pintype "passive"))
      (node (ref "C308") (pin "2") (pinfunction "2_2") (pintype "passive"))
      (node (ref "C309") (pin "2") (pinfunction "2_2") (pintype "passive"))
      (node (ref "C310") (pin "2") (pinfunction "2_2") (pintype "passive"))
      (node (ref "C311") (pin "2") (pinfunction "2_2") (pintype "passive"))
      (node (ref "C312") (pin "2") (pinfunction "2_2") (pintype "passive"))
      (node (ref "C313") (pin "2") (pinfunction "2_2") (pintype "passive"))
      (node (ref "C314") (pin "2") (pinfunction "2_2") (pintype "passive"))
      (node (ref "C315") (pin "2") (pinfunction "2_2") (pintype "passive"))
      (node (ref "C316") (pin "2") (pinfunction "2_2") (pintype "passive"))
      (node (ref "C317") (pin "2") (pinfunction "2_2") (pintype "passive"))
      (node (ref "C318") (pin "2") (pinfunction "2_2") (pintype "passive"))
      (node (ref "C320") (pin "2") (pinfunction "2_2") (pintype "passive"))
      (node (ref "C321") (pin "2") (pinfunction "2_2") (pintype "passive"))
      (node (ref "C323") (pin "2") (pinfunction "2_2") (pintype "passive"))
      (node (ref "C324") (pin "2") (pinfunction "2_2") (pintype "passive"))
      (node (ref "C326") (pin "2") (pinfunction "2_2") (pintype "passive"))
      (node (ref "C327") (pin "2") (pinfunction "2_2") (pintype "passive"))
      (node (ref "D101") (pin "1") (pinfunction "A1_1") (pintype "passive"))
      (node (ref "D102") (pin "1") (pinfunction "A1_1") (pintype "passive"))
      (node (ref "D103") (pin "1") (pinfunction "A1_1") (pintype "passive"))
      (node (ref "D104") (pin "1") (pinfunction "A1_1") (pintype "passive"))
      (node (ref "D201") (pin "1") (pinfunction "A1_1") (pintype "passive"))
      (node (ref "J201") (pin "1") (pinfunction "1_1") (pintype "passive"))
      (node (ref "J201") (pin "2") (pinfunction "2_2") (pintype "passive"))
      (node (ref "J202") (pin "1") (pinfunction "1_1") (pintype "passive"))
      (node (ref "J204") (pin "1") (pinfunction "GND_1") (pintype "passive"))
      (node (ref "J205") (pin "1") (pinfunction "GND_1") (pintype "passive"))
      (node (ref "L202") (pin "2") (pinfunction "2_2") (pintype "passive"))
      (node (ref "Q111") (pin "2") (pinfunction "E_2") (pintype "passive"))
      (node (ref "Q112") (pin "2") (pinfunction "E_2") (pintype "passive"))
      (node (ref "Q116") (pin "3") (pinfunction "C_3") (pintype "passive"))
      (node (ref "Q118") (pin "3") (pinfunction "C_3") (pintype "passive"))
      (node (ref "Q311") (pin "3") (pinfunction "C_3") (pintype "passive"))
      (node (ref "Q314") (pin "3") (pinfunction "C_3") (pintype "passive"))
      (node (ref "R210") (pin "1") (pinfunction "1_1") (pintype "passive"))
      (node (ref "SJ201") (pin "1") (pinfunction "1_1") (pintype "passive"))
      (node (ref "U101") (pin "11") (pinfunction "GND_11") (pintype "bidirectional"))
      (node (ref "U101") (pin "4") (pinfunction "RS2_4") (pintype "bidirectional"))
      (node (ref "U101") (pin "5") (pinfunction "RS1_5") (pintype "bidirectional"))
      (node (ref "U102") (pin "11") (pinfunction "GND_11") (pintype "bidirectional"))
      (node (ref "U102") (pin "4") (pinfunction "RS2_4") (pintype "bidirectional"))
      (node (ref "U102") (pin "5") (pinfunction "RS1_5") (pintype "bidirectional"))
      (node (ref "U103") (pin "2") (pinfunction "-_2") (pintype "input"))
      (node (ref "U104") (pin "2") (pinfunction "-_2") (pintype "input"))
      (node (ref "U105") (pin "5") (pinfunction "REF_5") (pintype "passive"))
      (node (ref "U106") (pin "5") (pinfunction "REF_5") (pintype "passive"))
      (node (ref "U107") (pin "5") (pinfunction "REF_5") (pintype "passive"))
      (node (ref "U108") (pin "5") (pinfunction "REF_5") (pintype "passive"))
      (node (ref "U109") (pin "4") (pinfunction "GND_4") (pintype "bidirectional"))
      (node (ref "U110") (pin "4") (pinfunction "GND_4") (pintype "bidirectional"))
      (node (ref "U201") (pin "2") (pinfunction "GND_2") (pintype "power_in"))
      (node (ref "U202") (pin "2") (pinfunction "GND_2") (pintype "power_in"))
      (node (ref "U203") (pin "2") (pinfunction "GND_2") (pintype "power_in"))
      (node (ref "U204") (pin "5") (pinfunction "REF_5") (pintype "passive"))
      (node (ref "U205") (pin "2") (pinfunction "GND_2") (pintype "passive"))
      (node (ref "U207") (pin "4") (pinfunction "GND_4") (pintype "bidirectional"))
      (node (ref "U208") (pin "4") (pinfunction "GND_4") (pintype "bidirectional"))
      (node (ref "U209") (pin "11") (pinfunction "12/15_11") (pintype "input"))
      (node (ref "U209") (pin "14") (pinfunction "GND_14") (pintype "power_in"))
      (node (ref "U209") (pin "2") (pinfunction "AGND_2") (pintype "power_in"))
      (node (ref "U301") (pin "5") (pinfunction "GND_5") (pintype "power_in"))
      (node (ref "U302") (pin "5") (pinfunction "GND_5") (pintype "power_in"))
      (node (ref "U303") (pin "5") (pinfunction "GND_5") (pintype "power_in"))
      (node (ref "U304") (pin "5") (pinfunction "GND_5") (pintype "power_in"))
      (node (ref "U305") (pin "5") (pinfunction "GND_5") (pintype "power_in"))
      (node (ref "U306") (pin "5") (pinfunction "GND_5") (pintype "power_in"))
      (node (ref "U307") (pin "2") (pinfunction "C1_2") (pintype "input"))
      (node (ref "U307") (pin "3") (pinfunction "C2_3") (pintype "input"))
    )
    (net (code "38") (name "GNDI") (class "Default")
      (node (ref "C319") (pin "2") (pinfunction "2_2") (pintype "passive"))
      (node (ref "C322") (pin "2") (pinfunction "2_2") (pintype "passive"))
      (node (ref "C325") (pin "2") (pinfunction "2_2") (pintype "passive"))
      (node (ref "C328") (pin "2") (pinfunction "2_2") (pintype "passive"))
      (node (ref "J203") (pin "15") (pinfunction "15_15") (pintype "passive"))
      (node (ref "Q301") (pin "3") (pinfunction "C_3") (pintype "passive"))
      (node (ref "Q302") (pin "3") (pinfunction "C_3") (pintype "passive"))
      (node (ref "Q303") (pin "3") (pinfunction "C_3") (pintype "passive"))
      (node (ref "Q304") (pin "3") (pinfunction "C_3") (pintype "passive"))
      (node (ref "Q305") (pin "3") (pinfunction "C_3") (pintype "passive"))
      (node (ref "Q306") (pin "3") (pinfunction "C_3") (pintype "passive"))
      (node (ref "Q307") (pin "3") (pinfunction "C_3") (pintype "passive"))
      (node (ref "Q308") (pin "3") (pinfunction "C_3") (pintype "passive"))
      (node (ref "Q309") (pin "3") (pinfunction "C_3") (pintype "passive"))
      (node (ref "Q310") (pin "3") (pinfunction "C_3") (pintype "passive"))
      (node (ref "Q312") (pin "3") (pinfunction "C_3") (pintype "passive"))
      (node (ref "Q313") (pin "3") (pinfunction "C_3") (pintype "passive"))
      (node (ref "U301") (pin "2") (pinfunction "C1_2") (pintype "input"))
      (node (ref "U301") (pin "3") (pinfunction "C2_3") (pintype "input"))
      (node (ref "U302") (pin "2") (pinfunction "C1_2") (pintype "input"))
      (node (ref "U302") (pin "3") (pinfunction "C2_3") (pintype "input"))
      (node (ref "U303") (pin "2") (pinfunction "C1_2") (pintype "input"))
      (node (ref "U303") (pin "3") (pinfunction "C2_3") (pintype "input"))
      (node (ref "U304") (pin "2") (pinfunction "C1_2") (pintype "input"))
      (node (ref "U304") (pin "3") (pinfunction "C2_3") (pintype "input"))
      (node (ref "U305") (pin "2") (pinfunction "C1_2") (pintype "input"))
      (node (ref "U305") (pin "3") (pinfunction "C2_3") (pintype "input"))
      (node (ref "U306") (pin "2") (pinfunction "C1_2") (pintype "input"))
      (node (ref "U306") (pin "3") (pinfunction "C2_3") (pintype "input"))
      (node (ref "U307") (pin "5") (pinfunction "GND_5") (pintype "power_in"))
    )
    (net (code "39") (name "LATCH_DAC") (class "Default")
      (node (ref "C327") (pin "1") (pinfunction "1_1") (pintype "passive"))
      (node (ref "R327") (pin "1") (pinfunction "1_1") (pintype "passive"))
      (node (ref "U101") (pin "7") (pinfunction "LATCH_7") (pintype "bidirectional"))
      (node (ref "U102") (pin "7") (pinfunction "LATCH_7") (pintype "bidirectional"))
      (node (ref "U306") (pin "6") (pinfunction "VO2_6") (pintype "output"))
    )
    (net (code "40") (name "LATCH_DAC_I") (class "Default")
      (node (ref "J203") (pin "5") (pinfunction "5_5") (pintype "passive"))
      (node (ref "Q313") (pin "1") (pinfunction "B_1") (pintype "passive"))
    )
    (net (code "41") (name "MISO") (class "Default")
      (node (ref "Q314") (pin "1") (pinfunction "B_1") (pintype "passive"))
      (node (ref "R1") (pin "1") (pinfunction "1_1") (pintype "passive"))
      (node (ref "U109") (pin "6") (pinfunction "SDO_6") (pintype "output"))
      (node (ref "U110") (pin "6") (pinfunction "SDO_6") (pintype "output"))
      (node (ref "U207") (pin "6") (pinfunction "SDO_6") (pintype "output"))
      (node (ref "U208") (pin "6") (pinfunction "SDO_6") (pintype "output"))
    )
    (net (code "42") (name "MISO_I") (class "Default")
      (node (ref "C328") (pin "1") (pinfunction "1_1") (pintype "passive"))
      (node (ref "J203") (pin "2") (pinfunction "2_2") (pintype "passive"))
      (node (ref "R328") (pin "1") (pinfunction "1_1") (pintype "passive"))
      (node (ref "U307") (pin "6") (pinfunction "VO2_6") (pintype "output"))
    )
    (net (code "43") (name "MOSI") (class "Default")
      (node (ref "C310") (pin "1") (pinfunction "1_1") (pintype "passive"))
      (node (ref "R310") (pin "1") (pinfunction "1_1") (pintype "passive"))
      (node (ref "U101") (pin "9") (pinfunction "SDI_9") (pintype "bidirectional"))
      (node (ref "U109") (pin "5") (pinfunction "SDI_5") (pintype "input"))
      (node (ref "U110") (pin "5") (pinfunction "SDI_5") (pintype "input"))
      (node (ref "U207") (pin "5") (pinfunction "SDI_5") (pintype "input"))
      (node (ref "U208") (pin "5") (pinfunction "SDI_5") (pintype "input"))
      (node (ref "U302") (pin "7") (pinfunction "VO1_7") (pintype "output"))
    )
    (net (code "44") (name "MOSI_I") (class "Default")
      (node (ref "J203") (pin "4") (pinfunction "4_4") (pintype "passive"))
      (node (ref "Q302") (pin "1") (pinfunction "B_1") (pintype "passive"))
    )
    (net (code "45") (name "Net-(D101-C1A2)") (class "Default")
      (node (ref "D101") (pin "3") (pinfunction "C1A2_3") (pintype "passive"))
      (node (ref "R135") (pin "1") (pinfunction "1_1") (pintype "passive"))
      (node (ref "U105") (pin "6") (pinfunction "OUT_6") (pintype "output"))
    )
    (net (code "46") (name "Net-(D102-C1A2)") (class "Default")
      (node (ref "D102") (pin "3") (pinfunction "C1A2_3") (pintype "passive"))
      (node (ref "R136") (pin "1") (pinfunction "1_1") (pintype "passive"))
      (node (ref "U106") (pin "6") (pinfunction "OUT_6") (pintype "output"))
    )
    (net (code "47") (name "Net-(D103-C1A2)") (class "Default")
      (node (ref "D103") (pin "3") (pinfunction "C1A2_3") (pintype "passive"))
      (node (ref "R137") (pin "1") (pinfunction "1_1") (pintype "passive"))
      (node (ref "U107") (pin "6") (pinfunction "OUT_6") (pintype "output"))
    )
    (net (code "48") (name "Net-(D104-C1A2)") (class "Default")
      (node (ref "D104") (pin "3") (pinfunction "C1A2_3") (pintype "passive"))
      (node (ref "R138") (pin "1") (pinfunction "1_1") (pintype "passive"))
      (node (ref "U108") (pin "6") (pinfunction "OUT_6") (pintype "output"))
    )
    (net (code "49") (name "Net-(D201-C1A2)") (class "Default")
      (node (ref "C218") (pin "1") (pinfunction "1_1") (pintype "passive"))
      (node (ref "D201") (pin "3") (pinfunction "C1A2_3") (pintype "passive"))
      (node (ref "R209") (pin "2") (pinfunction "2_2") (pintype "passive"))
      (node (ref "U208") (pin "2") (pinfunction "CH0_2") (pintype "input"))
    )
    (net (code "50") (name "Net-(MOV201-Pad2)") (class "Default")
      (node (ref "MOV201") (pin "2") (pinfunction "2_2") (pintype "passive"))
      (node (ref "MOV202") (pin "1") (pinfunction "1_1") (pintype "passive"))
    )
    (net (code "51") (name "Net-(Q101-B)") (class "Default")
      (node (ref "Q101") (pin "1") (pinfunction "B_1") (pintype "passive"))
      (node (ref "Q102") (pin "1") (pinfunction "B_1") (pintype "passive"))
      (node (ref "U103") (pin "6") (pinfunction "OUT_6") (pintype "output"))
    )
    (net (code "52") (name "Net-(Q101-E)") (class "Default")
      (node (ref "Q101") (pin "2") (pinfunction "E_2") (pintype "passive"))
      (node (ref "Q105") (pin "1") (pinfunction "B_1") (pintype "passive"))
      (node (ref "R103") (pin "1") (pinfunction "1_1") (pintype "passive"))
    )
    (net (code "53") (name "Net-(Q102-E)") (class "Default")
      (node (ref "Q102") (pin "2") (pinfunction "E_2") (pintype "passive"))
      (node (ref "Q106") (pin "1") (pinfunction "B_1") (pintype "passive"))
      (node (ref "R104") (pin "2") (pinfunction "2_2") (pintype "passive"))
    )
    (net (code "54") (name "Net-(Q103-B)") (class "Default")
      (node (ref "Q103") (pin "1") (pinfunction "B_1") (pintype "passive"))
      (node (ref "Q104") (pin "1") (pinfunction "B_1") (pintype "passive"))
      (node (ref "U104") (pin "6") (pinfunction "OUT_6") (pintype "output"))
    )
    (net (code "55") (name "Net-(Q103-E)") (class "Default")
      (node (ref "Q103") (pin "2") (pinfunction "E_2") (pintype "passive"))
      (node (ref "Q107") (pin "1") (pinfunction "B_1") (pintype "passive"))
      (node (ref "R105") (pin "1") (pinfunction "1_1") (pintype "passive"))
    )
    (net (code "56") (name "Net-(Q104-E)") (class "Default")
      (node (ref "Q104") (pin "2") (pinfunction "E_2") (pintype "passive"))
      (node (ref "Q108") (pin "1") (pinfunction "B_1") (pintype "passive"))
      (node (ref "R106") (pin "2") (pinfunction "2_2") (pintype "passive"))
    )
    (net (code "57") (name "Net-(Q105-E)") (class "Default")
      (node (ref "Q105") (pin "2") (pinfunction "E_2") (pintype "passive"))
      (node (ref "R107") (pin "2") (pinfunction "2_2") (pintype "passive"))
    )
    (net (code "58") (name "Net-(Q106-E)") (class "Default")
      (node (ref "Q106") (pin "2") (pinfunction "E_2") (pintype "passive"))
      (node (ref "R108") (pin "1") (pinfunction "1_1") (pintype "passive"))
    )
    (net (code "59") (name "Net-(Q107-E)") (class "Default")
      (node (ref "Q107") (pin "2") (pinfunction "E_2") (pintype "passive"))
      (node (ref "R109") (pin "2") (pinfunction "2_2") (pintype "passive"))
    )
    (net (code "60") (name "Net-(Q108-E)") (class "Default")
      (node (ref "Q108") (pin "2") (pinfunction "E_2") (pintype "passive"))
      (node (ref "R110") (pin "1") (pinfunction "1_1") (pintype "passive"))
    )
    (net (code "61") (name "Net-(Q109-G)") (class "Default")
      (node (ref "Q109") (pin "4") (pinfunction "G_4") (pintype "passive"))
      (node (ref "R112") (pin "2") (pinfunction "2_2") (pintype "passive"))
    )
    (net (code "62") (name "Net-(Q110-G)") (class "Default")
      (node (ref "Q110") (pin "4") (pinfunction "G_4") (pintype "passive"))
      (node (ref "R114") (pin "2") (pinfunction "2_2") (pintype "passive"))
    )
    (net (code "63") (name "Net-(Q111-B)") (class "Default")
      (node (ref "Q111") (pin "1") (pinfunction "B_1") (pintype "passive"))
      (node (ref "R111") (pin "2") (pinfunction "2_2") (pintype "passive"))
      (node (ref "R115") (pin "1") (pinfunction "1_1") (pintype "passive"))
    )
    (net (code "64") (name "Net-(Q111-C)") (class "Default")
      (node (ref "Q111") (pin "3") (pinfunction "C_3") (pintype "passive"))
      (node (ref "Q115") (pin "1") (pinfunction "B_1") (pintype "passive"))
      (node (ref "Q116") (pin "1") (pinfunction "B_1") (pintype "passive"))
      (node (ref "R117") (pin "1") (pinfunction "1_1") (pintype "passive"))
    )
    (net (code "65") (name "Net-(Q112-B)") (class "Default")
      (node (ref "Q112") (pin "1") (pinfunction "B_1") (pintype "passive"))
      (node (ref "R113") (pin "2") (pinfunction "2_2") (pintype "passive"))
      (node (ref "R116") (pin "1") (pinfunction "1_1") (pintype "passive"))
    )
    (net (code "66") (name "Net-(Q112-C)") (class "Default")
      (node (ref "Q112") (pin "3") (pinfunction "C_3") (pintype "passive"))
      (node (ref "Q117") (pin "1") (pinfunction "B_1") (pintype "passive"))
      (node (ref "Q118") (pin "1") (pinfunction "B_1") (pintype "passive"))
      (node (ref "R119") (pin "1") (pinfunction "1_1") (pintype "passive"))
    )
    (net (code "67") (name "Net-(Q113-G)") (class "Default")
      (node (ref "Q113") (pin "4") (pinfunction "G_4") (pintype "passive"))
      (node (ref "R118") (pin "2") (pinfunction "2_2") (pintype "passive"))
    )
    (net (code "68") (name "Net-(Q114-G)") (class "Default")
      (node (ref "Q114") (pin "4") (pinfunction "G_4") (pintype "passive"))
      (node (ref "R120") (pin "2") (pinfunction "2_2") (pintype "passive"))
    )
    (net (code "69") (name "Net-(Q115-E)") (class "Default")
      (node (ref "Q115") (pin "2") (pinfunction "E_2") (pintype "passive"))
      (node (ref "Q116") (pin "2") (pinfunction "E_2") (pintype "passive"))
      (node (ref "R114") (pin "1") (pinfunction "1_1") (pintype "passive"))
      (node (ref "R120") (pin "1") (pinfunction "1_1") (pintype "passive"))
      (node (ref "R127") (pin "2") (pinfunction "2_2") (pintype "passive"))
    )
    (net (code "70") (name "Net-(Q117-E)") (class "Default")
      (node (ref "Q117") (pin "2") (pinfunction "E_2") (pintype "passive"))
      (node (ref "Q118") (pin "2") (pinfunction "E_2") (pintype "passive"))
      (node (ref "R112") (pin "1") (pinfunction "1_1") (pintype "passive"))
      (node (ref "R118") (pin "1") (pinfunction "1_1") (pintype "passive"))
      (node (ref "R128") (pin "1") (pinfunction "1_1") (pintype "passive"))
    )
    (net (code "71") (name "Net-(Q119-G)") (class "Default")
      (node (ref "Q119") (pin "3") (pinfunction "G_3") (pintype "passive"))
      (node (ref "R107") (pin "1") (pinfunction "1_1") (pintype "passive"))
      (node (ref "R108") (pin "2") (pinfunction "2_2") (pintype "passive"))
    )
    (net (code "72") (name "Net-(Q120-G)") (class "Default")
      (node (ref "Q120") (pin "3") (pinfunction "G_3") (pintype "passive"))
      (node (ref "R109") (pin "1") (pinfunction "1_1") (pintype "passive"))
      (node (ref "R110") (pin "2") (pinfunction "2_2") (pintype "passive"))
    )
    (net (code "73") (name "Net-(Q201-B)") (class "Default")
      (node (ref "C237") (pin "1") (pinfunction "1_1") (pintype "passive"))
      (node (ref "Q201") (pin "1") (pinfunction "B_1") (pintype "passive"))
      (node (ref "R212") (pin "2") (pinfunction "2_2") (pintype "passive"))
    )
    (net (code "74") (name "Net-(Q201-C)") (class "Default")
      (node (ref "C235") (pin "-") (pinfunction "-_-") (pintype "passive"))
      (node (ref "D203") (pin "A") (pinfunction "A_A") (pintype "passive"))
      (node (ref "Q201") (pin "3") (pinfunction "C_3") (pintype "passive"))
      (node (ref "R212") (pin "1") (pinfunction "1_1") (pintype "passive"))
      (node (ref "U209") (pin "9") (pinfunction "FB-_9") (pintype "input"))
    )
    (net (code "75") (name "Net-(Q202-B)") (class "Default")
      (node (ref "C238") (pin "1") (pinfunction "1_1") (pintype "passive"))
      (node (ref "Q202") (pin "1") (pinfunction "B_1") (pintype "passive"))
      (node (ref "R211") (pin "2") (pinfunction "2_2") (pintype "passive"))
    )
    (net (code "76") (name "Net-(Q202-C)") (class "Default")
      (node (ref "C234") (pin "+") (pinfunction "+_+") (pintype "passive"))
      (node (ref "D202") (pin "C") (pinfunction "C_C") (pintype "passive"))
      (node (ref "Q202") (pin "3") (pinfunction "C_3") (pintype "passive"))
      (node (ref "R211") (pin "1") (pinfunction "1_1") (pintype "passive"))
      (node (ref "U209") (pin "16") (pinfunction "FB+_16") (pintype "input"))
    )
    (net (code "77") (name "Net-(Q301-E)") (class "Default")
      (node (ref "Q301") (pin "2") (pinfunction "E_2") (pintype "passive"))
      (node (ref "R301") (pin "1") (pinfunction "1_1") (pintype "passive"))
      (node (ref "U301") (pin "1") (pinfunction "A1_1") (pintype "input"))
    )
    (net (code "78") (name "Net-(Q302-E)") (class "Default")
      (node (ref "Q302") (pin "2") (pinfunction "E_2") (pintype "passive"))
      (node (ref "R302") (pin "1") (pinfunction "1_1") (pintype "passive"))
      (node (ref "U302") (pin "1") (pinfunction "A1_1") (pintype "input"))
    )
    (net (code "79") (name "Net-(Q303-E)") (class "Default")
      (node (ref "Q303") (pin "2") (pinfunction "E_2") (pintype "passive"))
      (node (ref "R303") (pin "1") (pinfunction "1_1") (pintype "passive"))
      (node (ref "U303") (pin "1") (pinfunction "A1_1") (pintype "input"))
    )
    (net (code "80") (name "Net-(Q304-E)") (class "Default")
      (node (ref "Q304") (pin "2") (pinfunction "E_2") (pintype "passive"))
      (node (ref "R304") (pin "1") (pinfunction "1_1") (pintype "passive"))
      (node (ref "U304") (pin "1") (pinfunction "A1_1") (pintype "input"))
    )
    (net (code "81") (name "Net-(Q305-E)") (class "Default")
      (node (ref "Q305") (pin "2") (pinfunction "E_2") (pintype "passive"))
      (node (ref "R305") (pin "1") (pinfunction "1_1") (pintype "passive"))
      (node (ref "U301") (pin "4") (pinfunction "A2_4") (pintype "input"))
    )
    (net (code "82") (name "Net-(Q306-E)") (class "Default")
      (node (ref "Q306") (pin "2") (pinfunction "E_2") (pintype "passive"))
      (node (ref "R306") (pin "1") (pinfunction "1_1") (pintype "passive"))
      (node (ref "U302") (pin "4") (pinfunction "A2_4") (pintype "input"))
    )
    (net (code "83") (name "Net-(Q307-E)") (class "Default")
      (node (ref "Q307") (pin "2") (pinfunction "E_2") (pintype "passive"))
      (node (ref "R307") (pin "1") (pinfunction "1_1") (pintype "passive"))
      (node (ref "U303") (pin "4") (pinfunction "A2_4") (pintype "input"))
    )
    (net (code "84") (name "Net-(Q308-E)") (class "Default")
      (node (ref "Q308") (pin "2") (pinfunction "E_2") (pintype "passive"))
      (node (ref "R308") (pin "1") (pinfunction "1_1") (pintype "passive"))
      (node (ref "U304") (pin "4") (pinfunction "A2_4") (pintype "input"))
    )
    (net (code "85") (name "Net-(Q309-E)") (class "Default")
      (node (ref "Q309") (pin "2") (pinfunction "E_2") (pintype "passive"))
      (node (ref "R317") (pin "1") (pinfunction "1_1") (pintype "passive"))
      (node (ref "U305") (pin "1") (pinfunction "A1_1") (pintype "input"))
    )
    (net (code "86") (name "Net-(Q310-E)") (class "Default")
      (node (ref "Q310") (pin "2") (pinfunction "E_2") (pintype "passive"))
      (node (ref "R318") (pin "1") (pinfunction "1_1") (pintype "passive"))
      (node (ref "U306") (pin "1") (pinfunction "A1_1") (pintype "input"))
    )
    (net (code "87") (name "Net-(Q311-E)") (class "Default")
      (node (ref "Q311") (pin "2") (pinfunction "E_2") (pintype "passive"))
      (node (ref "R319") (pin "1") (pinfunction "1_1") (pintype "passive"))
      (node (ref "U307") (pin "1") (pinfunction "A1_1") (pintype "input"))
    )
    (net (code "88") (name "Net-(Q312-E)") (class "Default")
      (node (ref "Q312") (pin "2") (pinfunction "E_2") (pintype "passive"))
      (node (ref "R320") (pin "1") (pinfunction "1_1") (pintype "passive"))
      (node (ref "U305") (pin "4") (pinfunction "A2_4") (pintype "input"))
    )
    (net (code "89") (name "Net-(Q313-E)") (class "Default")
      (node (ref "Q313") (pin "2") (pinfunction "E_2") (pintype "passive"))
      (node (ref "R321") (pin "1") (pinfunction "1_1") (pintype "passive"))
      (node (ref "U306") (pin "4") (pinfunction "A2_4") (pintype "input"))
    )
    (net (code "90") (name "Net-(Q314-E)") (class "Default")
      (node (ref "Q314") (pin "2") (pinfunction "E_2") (pintype "passive"))
      (node (ref "R322") (pin "1") (pinfunction "1_1") (pintype "passive"))
      (node (ref "U307") (pin "4") (pinfunction "A2_4") (pintype "input"))
    )
    (net (code "91") (name "Net-(R101-Pad1)") (class "Default")
      (node (ref "R101") (pin "1") (pinfunction "1_1") (pintype "passive"))
      (node (ref "U103") (pin "8") (pinfunction "RG_8") (pintype "passive"))
    )
    (net (code "92") (name "Net-(R101-Pad2)") (class "Default")
      (node (ref "R101") (pin "2") (pinfunction "2_2") (pintype "passive"))
      (node (ref "U103") (pin "1") (pinfunction "RG_1") (pintype "passive"))
    )
    (net (code "93") (name "Net-(R102-Pad1)") (class "Default")
      (node (ref "R102") (pin "1") (pinfunction "1_1") (pintype "passive"))
      (node (ref "U104") (pin "8") (pinfunction "RG_8") (pintype "passive"))
    )
    (net (code "94") (name "Net-(R102-Pad2)") (class "Default")
      (node (ref "R102") (pin "2") (pinfunction "2_2") (pintype "passive"))
      (node (ref "U104") (pin "1") (pinfunction "RG_1") (pintype "passive"))
    )
    (net (code "95") (name "Net-(R131-Pad1)") (class "Default")
      (node (ref "R131") (pin "1") (pinfunction "1_1") (pintype "passive"))
      (node (ref "U105") (pin "8") (pinfunction "RG_8") (pintype "passive"))
    )
    (net (code "96") (name "Net-(R131-Pad2)") (class "Default")
      (node (ref "R131") (pin "2") (pinfunction "2_2") (pintype "passive"))
      (node (ref "U105") (pin "1") (pinfunction "RG_1") (pintype "passive"))
    )
    (net (code "97") (name "Net-(R132-Pad1)") (class "Default")
      (node (ref "R132") (pin "1") (pinfunction "1_1") (pintype "passive"))
      (node (ref "U106") (pin "8") (pinfunction "RG_8") (pintype "passive"))
    )
    (net (code "98") (name "Net-(R132-Pad2)") (class "Default")
      (node (ref "R132") (pin "2") (pinfunction "2_2") (pintype "passive"))
      (node (ref "U106") (pin "1") (pinfunction "RG_1") (pintype "passive"))
    )
    (net (code "99") (name "Net-(R133-Pad1)") (class "Default")
      (node (ref "R133") (pin "1") (pinfunction "1_1") (pintype "passive"))
      (node (ref "U107") (pin "8") (pinfunction "RG_8") (pintype "passive"))
    )
    (net (code "100") (name "Net-(R133-Pad2)") (class "Default")
      (node (ref "R133") (pin "2") (pinfunction "2_2") (pintype "passive"))
      (node (ref "U107") (pin "1") (pinfunction "RG_1") (pintype "passive"))
    )
    (net (code "101") (name "Net-(R134-Pad1)") (class "Default")
      (node (ref "R134") (pin "1") (pinfunction "1_1") (pintype "passive"))
      (node (ref "U108") (pin "8") (pinfunction "RG_8") (pintype "passive"))
    )
    (net (code "102") (name "Net-(R134-Pad2)") (class "Default")
      (node (ref "R134") (pin "2") (pinfunction "2_2") (pintype "passive"))
      (node (ref "U108") (pin "1") (pinfunction "RG_1") (pintype "passive"))
    )
    (net (code "103") (name "Net-(R201-Pad2)") (class "Default")
      (node (ref "R201") (pin "2") (pinfunction "2_2") (pintype "passive"))
      (node (ref "R204") (pin "1") (pinfunction "1_1") (pintype "passive"))
    )
    (net (code "104") (name "Net-(R203-Pad1)") (class "Default")
      (node (ref "R203") (pin "1") (pinfunction "1_1") (pintype "passive"))
      (node (ref "R204") (pin "2") (pinfunction "2_2") (pintype "passive"))
    )
    (net (code "105") (name "Net-(R203-Pad2)") (class "Default")
      (node (ref "R203") (pin "2") (pinfunction "2_2") (pintype "passive"))
      (node (ref "R205") (pin "2") (pinfunction "2_2") (pintype "passive"))
    )
    (net (code "106") (name "Net-(R205-Pad1)") (class "Default")
      (node (ref "R205") (pin "1") (pinfunction "1_1") (pintype "passive"))
      (node (ref "R206") (pin "2") (pinfunction "2_2") (pintype "passive"))
    )
    (net (code "107") (name "Net-(R208-Pad1)") (class "Default")
      (node (ref "R208") (pin "1") (pinfunction "1_1") (pintype "passive"))
      (node (ref "U204") (pin "8") (pinfunction "RG_8") (pintype "passive"))
    )
    (net (code "108") (name "Net-(R208-Pad2)") (class "Default")
      (node (ref "R208") (pin "2") (pinfunction "2_2") (pintype "passive"))
      (node (ref "U204") (pin "1") (pinfunction "RG_1") (pintype "passive"))
    )
    (net (code "109") (name "Net-(U101-C1)") (class "Default")
      (node (ref "C109") (pin "2") (pinfunction "2_2") (pintype "passive"))
      (node (ref "U101") (pin "20") (pinfunction "C1_20") (pintype "bidirectional"))
    )
    (net (code "110") (name "Net-(U101-C2)") (class "Default")
      (node (ref "C107") (pin "2") (pinfunction "2_2") (pintype "passive"))
      (node (ref "U101") (pin "21") (pinfunction "C2_21") (pintype "bidirectional"))
    )
    (net (code "111") (name "Net-(U101-VOUT)") (class "Default")
      (node (ref "U101") (pin "17") (pinfunction "VOUT_17") (pintype "bidirectional"))
      (node (ref "U103") (pin "3") (pinfunction "+_3") (pintype "input"))
    )
    (net (code "112") (name "Net-(U102-C1)") (class "Default")
      (node (ref "C110") (pin "2") (pinfunction "2_2") (pintype "passive"))
      (node (ref "U102") (pin "20") (pinfunction "C1_20") (pintype "bidirectional"))
    )
    (net (code "113") (name "Net-(U102-C2)") (class "Default")
      (node (ref "C108") (pin "2") (pinfunction "2_2") (pintype "passive"))
      (node (ref "U102") (pin "21") (pinfunction "C2_21") (pintype "bidirectional"))
    )
    (net (code "114") (name "Net-(U102-VOUT)") (class "Default")
      (node (ref "U102") (pin "17") (pinfunction "VOUT_17") (pintype "bidirectional"))
      (node (ref "U104") (pin "3") (pinfunction "+_3") (pintype "input"))
    )
    (net (code "115") (name "Net-(U109-CH0)") (class "Default")
      (node (ref "C129") (pin "1") (pinfunction "1_1") (pintype "passive"))
      (node (ref "R135") (pin "2") (pinfunction "2_2") (pintype "passive"))
      (node (ref "U109") (pin "2") (pinfunction "CH0_2") (pintype "input"))
    )
    (net (code "116") (name "Net-(U109-CH1)") (class "Default")
      (node (ref "C130") (pin "1") (pinfunction "1_1") (pintype "passive"))
      (node (ref "R136") (pin "2") (pinfunction "2_2") (pintype "passive"))
      (node (ref "U109") (pin "3") (pinfunction "CH1_3") (pintype "input"))
    )
    (net (code "117") (name "Net-(U110-CH0)") (class "Default")
      (node (ref "C131") (pin "1") (pinfunction "1_1") (pintype "passive"))
      (node (ref "R137") (pin "2") (pinfunction "2_2") (pintype "passive"))
      (node (ref "U110") (pin "2") (pinfunction "CH0_2") (pintype "input"))
    )
    (net (code "118") (name "Net-(U110-CH1)") (class "Default")
      (node (ref "C132") (pin "1") (pinfunction "1_1") (pintype "passive"))
      (node (ref "R138") (pin "2") (pinfunction "2_2") (pintype "passive"))
      (node (ref "U110") (pin "3") (pinfunction "CH1_3") (pintype "input"))
    )
    (net (code "119") (name "Net-(U201-BYP)") (class "Default")
      (node (ref "C205") (pin "1") (pinfunction "1_1") (pintype "passive"))
      (node (ref "U201") (pin "4") (pinfunction "BYP_4") (pintype "power_in"))
    )
    (net (code "120") (name "Net-(U202-BYP)") (class "Default")
      (node (ref "C206") (pin "1") (pinfunction "1_1") (pintype "passive"))
      (node (ref "U202") (pin "4") (pinfunction "BYP_4") (pintype "power_in"))
    )
    (net (code "121") (name "Net-(U203-BYP)") (class "Default")
      (node (ref "C207") (pin "1") (pinfunction "1_1") (pintype "passive"))
      (node (ref "U203") (pin "4") (pinfunction "BYP_4") (pintype "power_in"))
    )
    (net (code "122") (name "Net-(U204-+)") (class "Default")
      (node (ref "R206") (pin "1") (pinfunction "1_1") (pintype "passive"))
      (node (ref "R207") (pin "2") (pinfunction "2_2") (pintype "passive"))
      (node (ref "U204") (pin "3") (pinfunction "+_3") (pintype "input"))
    )
    (net (code "123") (name "Net-(U204--)") (class "Default")
      (node (ref "R202") (pin "2") (pinfunction "2_2") (pintype "passive"))
      (node (ref "U204") (pin "2") (pinfunction "-_2") (pintype "input"))
    )
    (net (code "124") (name "Net-(U204-OUT)") (class "Default")
      (node (ref "R209") (pin "1") (pinfunction "1_1") (pintype "passive"))
      (node (ref "U204") (pin "6") (pinfunction "OUT_6") (pintype "output"))
    )
    (net (code "125") (name "Net-(U208-CH1)") (class "Default")
      (node (ref "R210") (pin "2") (pinfunction "2_2") (pintype "passive"))
      (node (ref "U208") (pin "3") (pinfunction "CH1_3") (pintype "input"))
    )
    (net (code "126") (name "Net-(U209-CC+)") (class "Default")
      (node (ref "C226") (pin "2") (pinfunction "2_2") (pintype "passive"))
      (node (ref "U209") (pin "1") (pinfunction "CC+_1") (pintype "passive"))
    )
    (net (code "127") (name "Net-(U209-CC-)") (class "Default")
      (node (ref "C231") (pin "1") (pinfunction "1_1") (pintype "passive"))
      (node (ref "U209") (pin "8") (pinfunction "CC-_8") (pintype "passive"))
    )
    (net (code "128") (name "Net-(U209-LX+)") (class "Default")
      (node (ref "D202") (pin "A") (pinfunction "A_A") (pintype "passive"))
      (node (ref "L201") (pin "2") (pinfunction "2_2") (pintype "passive"))
      (node (ref "U209") (pin "15") (pinfunction "LX+_15") (pintype "passive"))
    )
    (net (code "129") (name "Net-(U209-LX-)") (class "Default")
      (node (ref "D203") (pin "C") (pinfunction "C_C") (pintype "passive"))
      (node (ref "L202") (pin "1") (pinfunction "1_1") (pintype "passive"))
      (node (ref "U209") (pin "10") (pinfunction "LX-_10") (pintype "passive"))
    )
    (net (code "130") (name "Net-(U209-SS)") (class "Default")
      (node (ref "C230") (pin "1") (pinfunction "1_1") (pintype "passive"))
      (node (ref "U209") (pin "7") (pinfunction "SS_7") (pintype "passive"))
    )
    (net (code "131") (name "Net-(U209-VREF)") (class "Default")
      (node (ref "C227") (pin "+") (pinfunction "+_+") (pintype "passive"))
      (node (ref "U209") (pin "6") (pinfunction "VREF_6") (pintype "power_in"))
    )
    (net (code "132") (name "SCK") (class "Default")
      (node (ref "C314") (pin "1") (pinfunction "1_1") (pintype "passive"))
      (node (ref "R314") (pin "1") (pinfunction "1_1") (pintype "passive"))
      (node (ref "U101") (pin "8") (pinfunction "SCK_8") (pintype "bidirectional"))
      (node (ref "U102") (pin "8") (pinfunction "SCK_8") (pintype "bidirectional"))
      (node (ref "U109") (pin "7") (pinfunction "SCK_7") (pintype "input"))
      (node (ref "U110") (pin "7") (pinfunction "SCK_7") (pintype "input"))
      (node (ref "U207") (pin "7") (pinfunction "SCK_7") (pintype "input"))
      (node (ref "U208") (pin "7") (pinfunction "SCK_7") (pintype "input"))
      (node (ref "U302") (pin "6") (pinfunction "VO2_6") (pintype "output"))
    )
    (net (code "133") (name "SCK_I") (class "Default")
      (node (ref "J203") (pin "3") (pinfunction "3_3") (pintype "passive"))
      (node (ref "Q306") (pin "1") (pinfunction "B_1") (pintype "passive"))
    )
    (net (code "134") (name "SDO_DAC1") (class "Default")
      (node (ref "U101") (pin "10") (pinfunction "SDO_10") (pintype "bidirectional"))
      (node (ref "U102") (pin "9") (pinfunction "SDI_9") (pintype "bidirectional"))
    )
    (net (code "135") (name "SDO_DAC2") (class "Default")
      (node (ref "U102") (pin "10") (pinfunction "SDO_10") (pintype "bidirectional"))
    )
    (net (code "136") (name "TEMP1") (class "Default")
      (node (ref "C211") (pin "1") (pinfunction "1_1") (pintype "passive"))
      (node (ref "J201") (pin "5") (pinfunction "5_5") (pintype "passive"))
      (node (ref "U207") (pin "2") (pinfunction "CH0_2") (pintype "input"))
    )
    (net (code "137") (name "TEMP2") (class "Default")
      (node (ref "C215") (pin "1") (pinfunction "1_1") (pintype "passive"))
      (node (ref "J201") (pin "6") (pinfunction "6_6") (pintype "passive"))
      (node (ref "U207") (pin "3") (pinfunction "CH1_3") (pintype "input"))
    )
    (net (code "138") (name "VREF1") (class "Default")
      (node (ref "C201") (pin "1") (pinfunction "1_1") (pintype "passive"))
      (node (ref "U101") (pin "14") (pinfunction "REF_OUT_14") (pintype "bidirectional"))
      (node (ref "U101") (pin "15") (pinfunction "REF_IN_15") (pintype "bidirectional"))
      (node (ref "U201") (pin "1") (pinfunction "VIN_1") (pintype "power_in"))
      (node (ref "U201") (pin "3") (pinfunction "ON/OFF_3") (pintype "input"))
    )
    (net (code "139") (name "VREF2") (class "Default")
      (node (ref "C202") (pin "1") (pinfunction "1_1") (pintype "passive"))
      (node (ref "U102") (pin "14") (pinfunction "REF_OUT_14") (pintype "bidirectional"))
      (node (ref "U102") (pin "15") (pinfunction "REF_IN_15") (pintype "bidirectional"))
      (node (ref "U202") (pin "1") (pinfunction "VIN_1") (pintype "power_in"))
      (node (ref "U202") (pin "3") (pinfunction "ON/OFF_3") (pintype "input"))
    )
    (net (code "140") (name "VSENSE+") (class "Default")
      (node (ref "J206") (pin "1") (pinfunction "1_1") (pintype "passive"))
      (node (ref "MOV201") (pin "1") (pinfunction "1_1") (pintype "passive"))
      (node (ref "R201") (pin "1") (pinfunction "1_1") (pintype "passive"))
    )
    (net (code "141") (name "VSENSE-") (class "Default")
      (node (ref "J207") (pin "2") (pinfunction "1_2") (pintype "passive"))
      (node (ref "MOV202") (pin "2") (pinfunction "2_2") (pintype "passive"))
      (node (ref "R202") (pin "1") (pinfunction "1_1") (pintype "passive"))
      (node (ref "R207") (pin "1") (pinfunction "1_1") (pintype "passive"))
    )
    (net (code "142") (name "unconnected-(J202-Pad2)") (class "Default")
      (node (ref "J202") (pin "2") (pinfunction "2_2") (pintype "passive"))
    )
    (net (code "143") (name "unconnected-(U101-BST-Pad19)") (class "Default")
      (node (ref "U101") (pin "19") (pinfunction "BST_19") (pintype "bidirectional"))
    )
    (net (code "144") (name "unconnected-(U101-IOUT-Pad18)") (class "Default")
      (node (ref "U101") (pin "18") (pinfunction "IOUT_18") (pintype "bidirectional"))
    )
    (net (code "145") (name "unconnected-(U101-O_TRIM-Pad16)") (class "Default")
      (node (ref "U101") (pin "16") (pinfunction "O_TRIM_16") (pintype "bidirectional"))
    )
    (net (code "146") (name "unconnected-(U102-BST-Pad19)") (class "Default")
      (node (ref "U102") (pin "19") (pinfunction "BST_19") (pintype "bidirectional"))
    )
    (net (code "147") (name "unconnected-(U102-IOUT-Pad18)") (class "Default")
      (node (ref "U102") (pin "18") (pinfunction "IOUT_18") (pintype "bidirectional"))
    )
    (net (code "148") (name "unconnected-(U102-O_TRIM-Pad16)") (class "Default")
      (node (ref "U102") (pin "16") (pinfunction "O_TRIM_16") (pintype "bidirectional"))
    )
  )
)
